# Control_Board.net
KiCad netlist of a schematic drawn in EAGLE
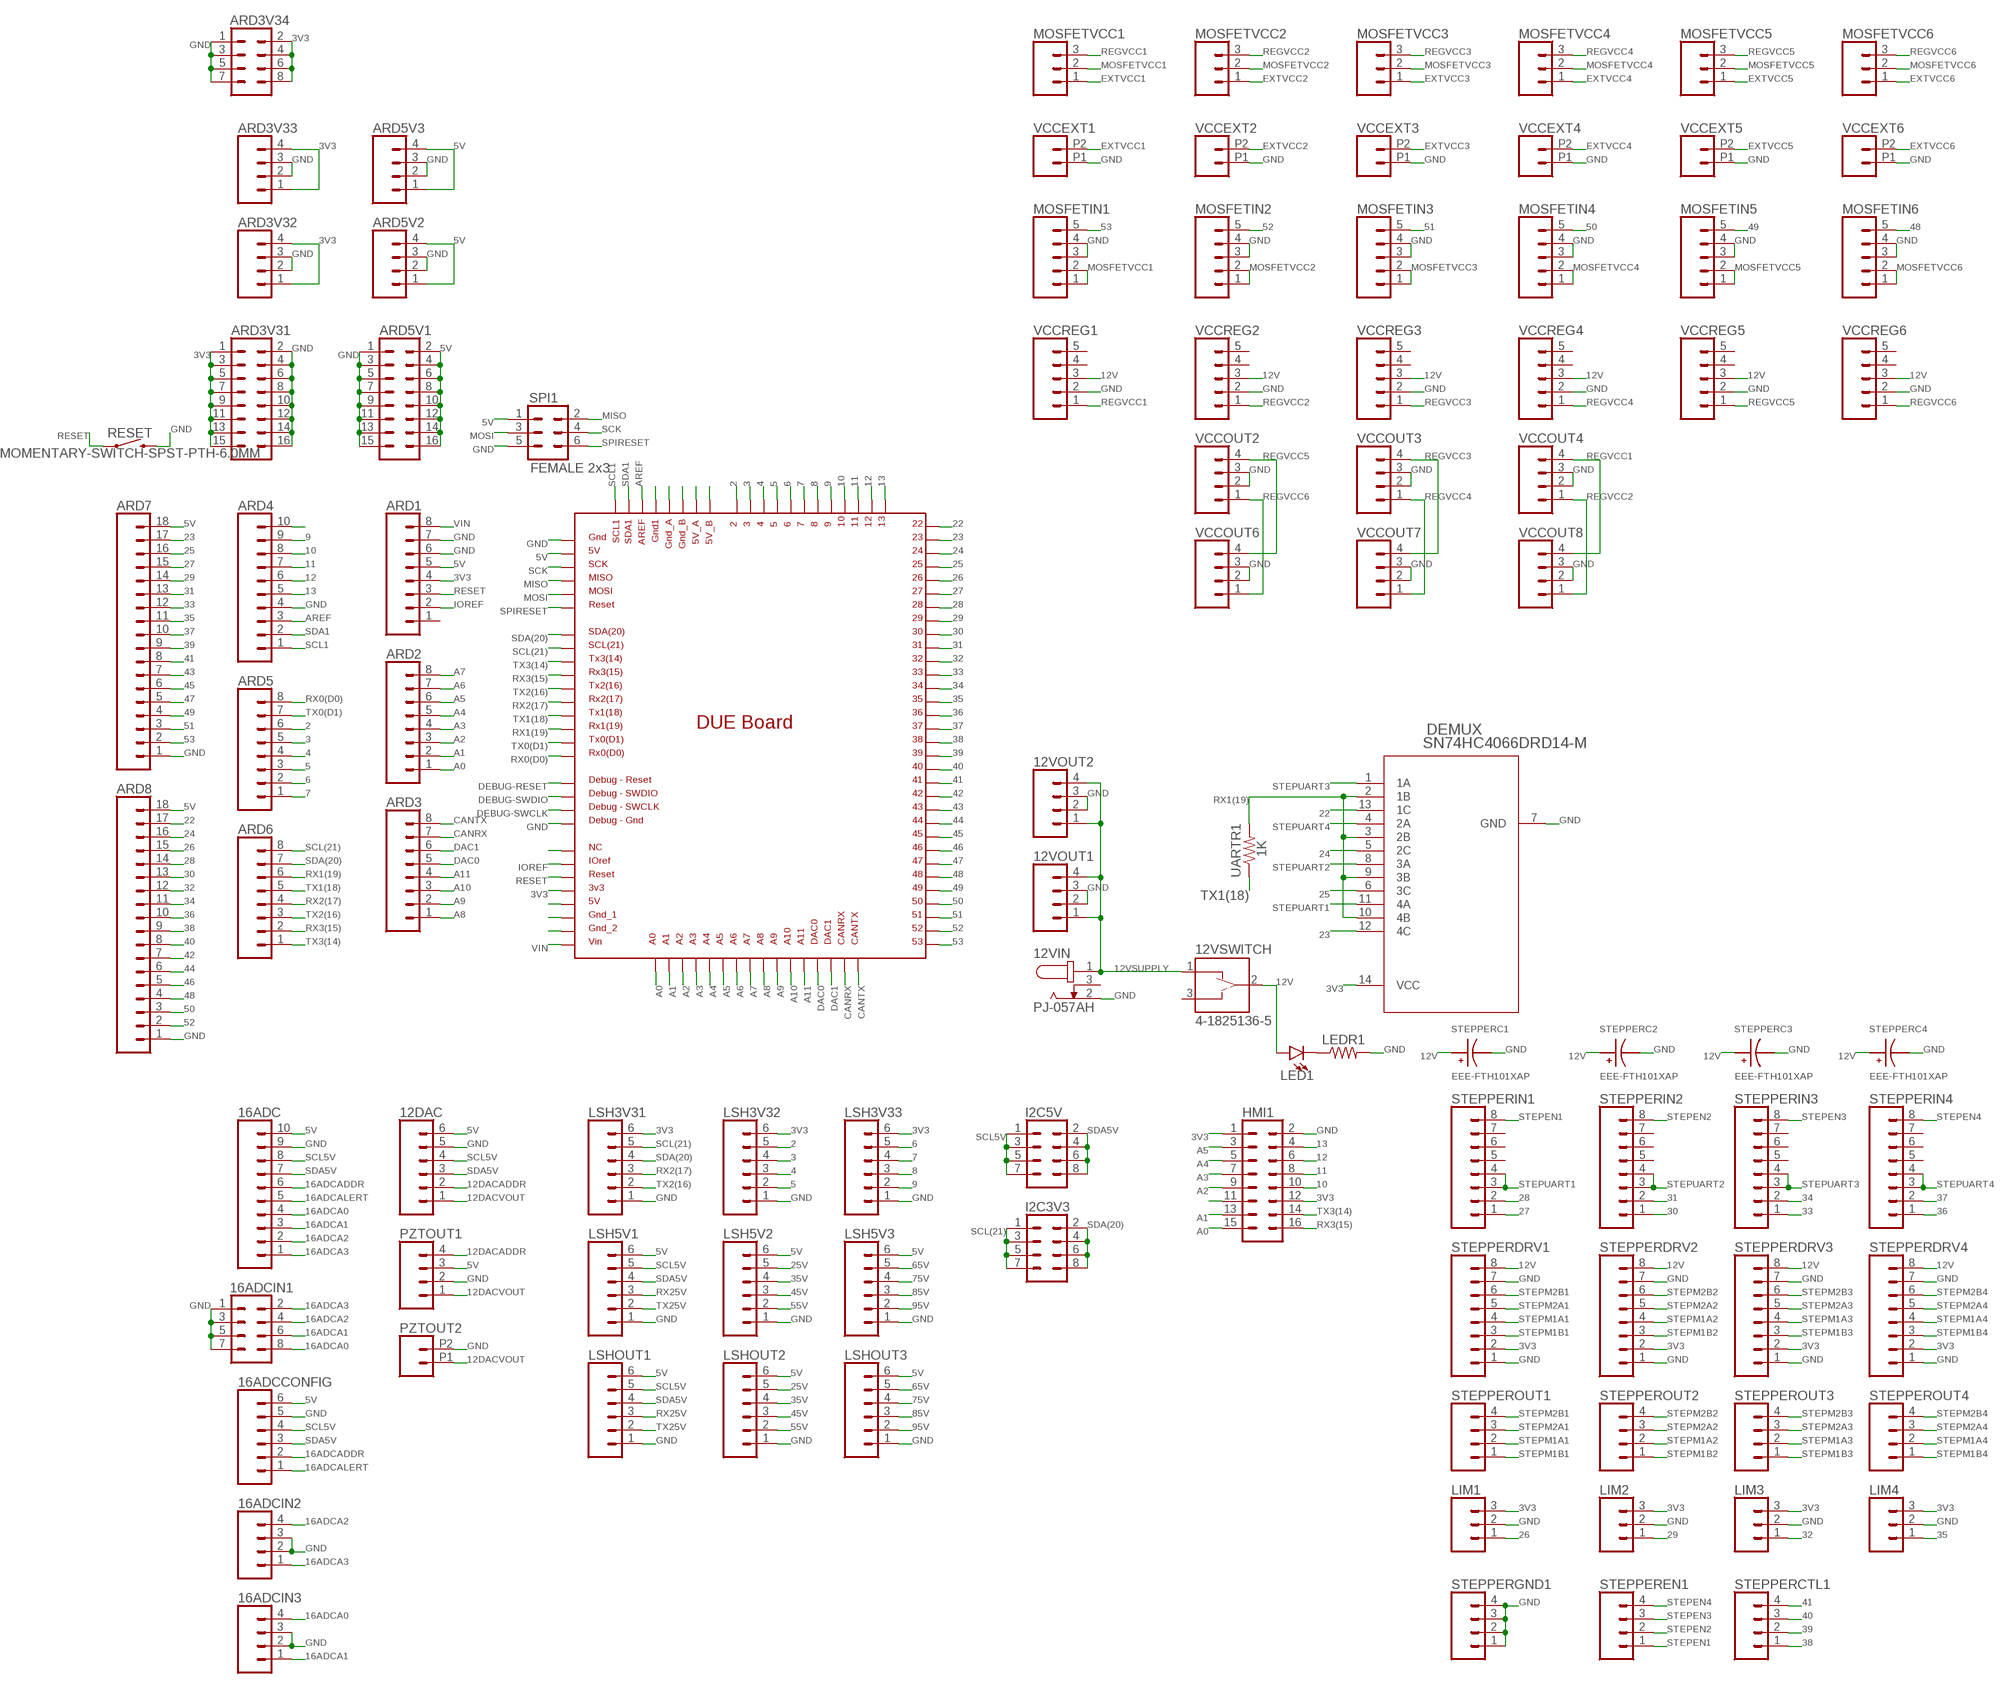
[diagram p0: schematic, sheet 1]

(export (version "E")
  (design (tool "Eeschema 10.0.6"))
  (components
    (comp (ref "12DAC")
      (value "CONN_06LOCK")
      (footprint "eagle-import:1X06_LOCK")
      (libsource (lib "eagle-import") (part "CONN_06LOCK"))
    )
    (comp (ref "12VIN")
      (value "PJ-057AH")
      (footprint "eagle-import:CUI_PJ-057AH")
      (fields (field (name "DIGI-KEY_PART_NUMBER") "CP-057AH-ND") (field (name "MF") "CUI Inc."))
      (libsource (lib "eagle-import") (part "PJ-057AH"))
    )
    (comp (ref "12VOUT1")
      (value "CONN_04POLAR")
      (footprint "eagle-import:MOLEX-1X4")
      (libsource (lib "eagle-import") (part "CONN_04POLAR"))
    )
    (comp (ref "12VOUT2")
      (value "CONN_04POLAR")
      (footprint "eagle-import:MOLEX-1X4")
      (libsource (lib "eagle-import") (part "CONN_04POLAR"))
    )
    (comp (ref "12VSWITCH")
      (value "4-1825136-5")
      (footprint "eagle-import:TE_4-1825136-5")
      (fields (field (name "DIGI-KEY_PART_NUMBER") "450-1784-ND") (field (name "MF") "TE Connectivity"))
      (libsource (lib "eagle-import") (part "4-1825136-5"))
    )
    (comp (ref "16ADC")
      (value "CONN_10LOCK")
      (footprint "eagle-import:1X10_LOCK")
      (libsource (lib "eagle-import") (part "CONN_10LOCK"))
    )
    (comp (ref "16ADCCONFIG")
      (value "CONN_06LOCK")
      (footprint "eagle-import:1X06_LOCK")
      (libsource (lib "eagle-import") (part "CONN_06LOCK"))
    )
    (comp (ref "16ADCIN1")
      (value "CONN_04X2")
      (footprint "eagle-import:2X4")
      (libsource (lib "eagle-import") (part "CONN_04X2"))
    )
    (comp (ref "16ADCIN2")
      (value "CONN_04POLAR")
      (footprint "eagle-import:MOLEX-1X4")
      (libsource (lib "eagle-import") (part "CONN_04POLAR"))
    )
    (comp (ref "16ADCIN3")
      (value "CONN_04POLAR")
      (footprint "eagle-import:MOLEX-1X4")
      (libsource (lib "eagle-import") (part "CONN_04POLAR"))
    )
    (comp (ref "ARD1")
      (value "CONN_08LOCK")
      (footprint "eagle-import:1X08_LOCK")
      (libsource (lib "eagle-import") (part "CONN_08LOCK"))
    )
    (comp (ref "ARD2")
      (value "CONN_08LOCK")
      (footprint "eagle-import:1X08_LOCK")
      (libsource (lib "eagle-import") (part "CONN_08LOCK"))
    )
    (comp (ref "ARD3")
      (value "CONN_08LOCK")
      (footprint "eagle-import:1X08_LOCK")
      (libsource (lib "eagle-import") (part "CONN_08LOCK"))
    )
    (comp (ref "ARD3V31")
      (value "CONN_08X2")
      (footprint "eagle-import:2X8")
      (libsource (lib "eagle-import") (part "CONN_08X2"))
    )
    (comp (ref "ARD3V32")
      (value "CONN_04POLAR")
      (footprint "eagle-import:MOLEX-1X4")
      (libsource (lib "eagle-import") (part "CONN_04POLAR"))
    )
    (comp (ref "ARD3V33")
      (value "CONN_04POLAR")
      (footprint "eagle-import:MOLEX-1X4")
      (libsource (lib "eagle-import") (part "CONN_04POLAR"))
    )
    (comp (ref "ARD3V34")
      (value "CONN_04X2")
      (footprint "eagle-import:2X4")
      (libsource (lib "eagle-import") (part "CONN_04X2"))
    )
    (comp (ref "ARD4")
      (value "CONN_10LOCK")
      (footprint "eagle-import:1X10_LOCK")
      (libsource (lib "eagle-import") (part "CONN_10LOCK"))
    )
    (comp (ref "ARD5")
      (value "CONN_08LOCK")
      (footprint "eagle-import:1X08_LOCK")
      (libsource (lib "eagle-import") (part "CONN_08LOCK"))
    )
    (comp (ref "ARD5V1")
      (value "CONN_08X2")
      (footprint "eagle-import:2X8")
      (libsource (lib "eagle-import") (part "CONN_08X2"))
    )
    (comp (ref "ARD5V2")
      (value "CONN_04POLAR")
      (footprint "eagle-import:MOLEX-1X4")
      (libsource (lib "eagle-import") (part "CONN_04POLAR"))
    )
    (comp (ref "ARD5V3")
      (value "CONN_04POLAR")
      (footprint "eagle-import:MOLEX-1X4")
      (libsource (lib "eagle-import") (part "CONN_04POLAR"))
    )
    (comp (ref "ARD6")
      (value "CONN_08LOCK")
      (footprint "eagle-import:1X08_LOCK")
      (libsource (lib "eagle-import") (part "CONN_08LOCK"))
    )
    (comp (ref "ARD7")
      (value "CONN_18")
      (footprint "eagle-import:1X18")
      (libsource (lib "eagle-import") (part "CONN_18"))
    )
    (comp (ref "ARD8")
      (value "CONN_18")
      (footprint "eagle-import:1X18")
      (libsource (lib "eagle-import") (part "CONN_18"))
    )
    (comp (ref "DEMUX")
      (value "SN74HC4066DRD14-M")
      (footprint "eagle-import:D14-M")
      (fields (field (name "MANUFACTURER_PART_NUMBER") "SN74HC4066DR"))
      (libsource (lib "eagle-import") (part "SN74HC4066DRD14-M"))
    )
    (comp (ref "HMI1")
      (value "CONN_08X2")
      (footprint "eagle-import:2X8")
      (libsource (lib "eagle-import") (part "CONN_08X2"))
    )
    (comp (ref "I2C3V3")
      (value "CONN_04X2")
      (footprint "eagle-import:2X4")
      (libsource (lib "eagle-import") (part "CONN_04X2"))
    )
    (comp (ref "I2C5V")
      (value "CONN_04X2")
      (footprint "eagle-import:2X4")
      (libsource (lib "eagle-import") (part "CONN_04X2"))
    )
    (comp (ref "LED1")
      (value "LED3MM")
      (footprint "eagle-import:LED_3MM")
      (libsource (lib "eagle-import") (part "LED3MM"))
    )
    (comp (ref "LEDR1")
      (value "RESISTORAXIAL-0.3")
      (footprint "eagle-import:AXIAL-0.3")
      (libsource (lib "eagle-import") (part "RESISTORAXIAL-0.3"))
    )
    (comp (ref "LIM1")
      (value "CONN_03LOCK")
      (footprint "eagle-import:1X03_LOCK")
      (libsource (lib "eagle-import") (part "CONN_03LOCK"))
    )
    (comp (ref "LIM2")
      (value "CONN_03LOCK")
      (footprint "eagle-import:1X03_LOCK")
      (libsource (lib "eagle-import") (part "CONN_03LOCK"))
    )
    (comp (ref "LIM3")
      (value "CONN_03LOCK")
      (footprint "eagle-import:1X03_LOCK")
      (libsource (lib "eagle-import") (part "CONN_03LOCK"))
    )
    (comp (ref "LIM4")
      (value "CONN_03LOCK")
      (footprint "eagle-import:1X03_LOCK")
      (libsource (lib "eagle-import") (part "CONN_03LOCK"))
    )
    (comp (ref "LSH3V31")
      (value "CONN_06NO_SILK_FEMALE_PTH")
      (footprint "eagle-import:1X06_NO_SILK")
      (libsource (lib "eagle-import") (part "CONN_06NO_SILK_FEMALE_PTH"))
    )
    (comp (ref "LSH3V32")
      (value "CONN_06NO_SILK_FEMALE_PTH")
      (footprint "eagle-import:1X06_NO_SILK")
      (libsource (lib "eagle-import") (part "CONN_06NO_SILK_FEMALE_PTH"))
    )
    (comp (ref "LSH3V33")
      (value "CONN_06NO_SILK_FEMALE_PTH")
      (footprint "eagle-import:1X06_NO_SILK")
      (libsource (lib "eagle-import") (part "CONN_06NO_SILK_FEMALE_PTH"))
    )
    (comp (ref "LSH5V1")
      (value "CONN_06NO_SILK_FEMALE_PTH")
      (footprint "eagle-import:1X06_NO_SILK")
      (libsource (lib "eagle-import") (part "CONN_06NO_SILK_FEMALE_PTH"))
    )
    (comp (ref "LSH5V2")
      (value "CONN_06NO_SILK_FEMALE_PTH")
      (footprint "eagle-import:1X06_NO_SILK")
      (libsource (lib "eagle-import") (part "CONN_06NO_SILK_FEMALE_PTH"))
    )
    (comp (ref "LSH5V3")
      (value "CONN_06NO_SILK_FEMALE_PTH")
      (footprint "eagle-import:1X06_NO_SILK")
      (libsource (lib "eagle-import") (part "CONN_06NO_SILK_FEMALE_PTH"))
    )
    (comp (ref "LSHOUT1")
      (value "CONN_06LOCK")
      (footprint "eagle-import:1X06_LOCK")
      (libsource (lib "eagle-import") (part "CONN_06LOCK"))
    )
    (comp (ref "LSHOUT2")
      (value "CONN_06LOCK")
      (footprint "eagle-import:1X06_LOCK")
      (libsource (lib "eagle-import") (part "CONN_06LOCK"))
    )
    (comp (ref "LSHOUT3")
      (value "CONN_06LOCK")
      (footprint "eagle-import:1X06_LOCK")
      (libsource (lib "eagle-import") (part "CONN_06LOCK"))
    )
    (comp (ref "MOSFETIN1")
      (value "CONN_05LOCK")
      (footprint "eagle-import:1X05_LOCK")
      (libsource (lib "eagle-import") (part "CONN_05LOCK"))
    )
    (comp (ref "MOSFETIN2")
      (value "CONN_05LOCK")
      (footprint "eagle-import:1X05_LOCK")
      (libsource (lib "eagle-import") (part "CONN_05LOCK"))
    )
    (comp (ref "MOSFETIN3")
      (value "CONN_05LOCK")
      (footprint "eagle-import:1X05_LOCK")
      (libsource (lib "eagle-import") (part "CONN_05LOCK"))
    )
    (comp (ref "MOSFETIN4")
      (value "CONN_05LOCK")
      (footprint "eagle-import:1X05_LOCK")
      (libsource (lib "eagle-import") (part "CONN_05LOCK"))
    )
    (comp (ref "MOSFETIN5")
      (value "CONN_05LOCK")
      (footprint "eagle-import:1X05_LOCK")
      (libsource (lib "eagle-import") (part "CONN_05LOCK"))
    )
    (comp (ref "MOSFETIN6")
      (value "CONN_05LOCK")
      (footprint "eagle-import:1X05_LOCK")
      (libsource (lib "eagle-import") (part "CONN_05LOCK"))
    )
    (comp (ref "MOSFETVCC1")
      (value "CONN_03LOCK")
      (footprint "eagle-import:1X03_LOCK")
      (libsource (lib "eagle-import") (part "CONN_03LOCK"))
    )
    (comp (ref "MOSFETVCC2")
      (value "CONN_03LOCK")
      (footprint "eagle-import:1X03_LOCK")
      (libsource (lib "eagle-import") (part "CONN_03LOCK"))
    )
    (comp (ref "MOSFETVCC3")
      (value "CONN_03LOCK")
      (footprint "eagle-import:1X03_LOCK")
      (libsource (lib "eagle-import") (part "CONN_03LOCK"))
    )
    (comp (ref "MOSFETVCC4")
      (value "CONN_03LOCK")
      (footprint "eagle-import:1X03_LOCK")
      (libsource (lib "eagle-import") (part "CONN_03LOCK"))
    )
    (comp (ref "MOSFETVCC5")
      (value "CONN_03LOCK")
      (footprint "eagle-import:1X03_LOCK")
      (libsource (lib "eagle-import") (part "CONN_03LOCK"))
    )
    (comp (ref "MOSFETVCC6")
      (value "CONN_03LOCK")
      (footprint "eagle-import:1X03_LOCK")
      (libsource (lib "eagle-import") (part "CONN_03LOCK"))
    )
    (comp (ref "PZTOUT1")
      (value "CONN_04LOCK")
      (footprint "eagle-import:1X04_LOCK")
      (libsource (lib "eagle-import") (part "CONN_04LOCK"))
    )
    (comp (ref "PZTOUT2")
      (value "CONN_022.54MM_SCREWTERM")
      (footprint "eagle-import:1X02_2.54_SCREWTERM")
      (libsource (lib "eagle-import") (part "CONN_022.54MM_SCREWTERM"))
    )
    (comp (ref "RESET")
      (value "MOMENTARY-SWITCH-SPST-PTH-6.0MM")
      (footprint "eagle-import:TACTILE_SWITCH_PTH_6.0MM")
      (libsource (lib "eagle-import") (part "MOMENTARY-SWITCH-SPST-PTH-6.0MM"))
    )
    (comp (ref "SPI1")
      (value "FEMALE 2x3")
      (footprint "eagle-import:2X3")
      (libsource (lib "eagle-import") (part "CONN_03X2FEMALE"))
    )
    (comp (ref "STEPPERC1")
      (value "EEE-FTH101XAP")
      (footprint "eagle-import:CAPAE660X800N")
      (fields (field (name "DIGI-KEY_PART_NUMBER") "PCE5024CT-ND") (field (name "MF") "Panasonic Electronic"))
      (libsource (lib "eagle-import") (part "EEE-FTH101XAP"))
    )
    (comp (ref "STEPPERC2")
      (value "EEE-FTH101XAP")
      (footprint "eagle-import:CAPAE660X800N")
      (fields (field (name "DIGI-KEY_PART_NUMBER") "PCE5024CT-ND") (field (name "MF") "Panasonic Electronic"))
      (libsource (lib "eagle-import") (part "EEE-FTH101XAP"))
    )
    (comp (ref "STEPPERC3")
      (value "EEE-FTH101XAP")
      (footprint "eagle-import:CAPAE660X800N")
      (fields (field (name "DIGI-KEY_PART_NUMBER") "PCE5024CT-ND") (field (name "MF") "Panasonic Electronic"))
      (libsource (lib "eagle-import") (part "EEE-FTH101XAP"))
    )
    (comp (ref "STEPPERC4")
      (value "EEE-FTH101XAP")
      (footprint "eagle-import:CAPAE660X800N")
      (fields (field (name "DIGI-KEY_PART_NUMBER") "PCE5024CT-ND") (field (name "MF") "Panasonic Electronic"))
      (libsource (lib "eagle-import") (part "EEE-FTH101XAP"))
    )
    (comp (ref "STEPPERCTL1")
      (value "CONN_04LOCK")
      (footprint "eagle-import:1X04_LOCK")
      (libsource (lib "eagle-import") (part "CONN_04LOCK"))
    )
    (comp (ref "STEPPERDRV1")
      (value "CONN_08NO_SILK_FEMALE_PTH")
      (footprint "eagle-import:1X08_NO_SILK")
      (libsource (lib "eagle-import") (part "CONN_08NO_SILK_FEMALE_PTH"))
    )
    (comp (ref "STEPPERDRV2")
      (value "CONN_08NO_SILK_FEMALE_PTH")
      (footprint "eagle-import:1X08_NO_SILK")
      (libsource (lib "eagle-import") (part "CONN_08NO_SILK_FEMALE_PTH"))
    )
    (comp (ref "STEPPERDRV3")
      (value "CONN_08NO_SILK_FEMALE_PTH")
      (footprint "eagle-import:1X08_NO_SILK")
      (libsource (lib "eagle-import") (part "CONN_08NO_SILK_FEMALE_PTH"))
    )
    (comp (ref "STEPPERDRV4")
      (value "CONN_08NO_SILK_FEMALE_PTH")
      (footprint "eagle-import:1X08_NO_SILK")
      (libsource (lib "eagle-import") (part "CONN_08NO_SILK_FEMALE_PTH"))
    )
    (comp (ref "STEPPEREN1")
      (value "CONN_04LOCK")
      (footprint "eagle-import:1X04_LOCK")
      (libsource (lib "eagle-import") (part "CONN_04LOCK"))
    )
    (comp (ref "STEPPERGND1")
      (value "CONN_04LOCK")
      (footprint "eagle-import:1X04_LOCK")
      (libsource (lib "eagle-import") (part "CONN_04LOCK"))
    )
    (comp (ref "STEPPERIN1")
      (value "CONN_08NO_SILK_FEMALE_PTH")
      (footprint "eagle-import:1X08_NO_SILK")
      (libsource (lib "eagle-import") (part "CONN_08NO_SILK_FEMALE_PTH"))
    )
    (comp (ref "STEPPERIN2")
      (value "CONN_08NO_SILK_FEMALE_PTH")
      (footprint "eagle-import:1X08_NO_SILK")
      (libsource (lib "eagle-import") (part "CONN_08NO_SILK_FEMALE_PTH"))
    )
    (comp (ref "STEPPERIN3")
      (value "CONN_08NO_SILK_FEMALE_PTH")
      (footprint "eagle-import:1X08_NO_SILK")
      (libsource (lib "eagle-import") (part "CONN_08NO_SILK_FEMALE_PTH"))
    )
    (comp (ref "STEPPERIN4")
      (value "CONN_08NO_SILK_FEMALE_PTH")
      (footprint "eagle-import:1X08_NO_SILK")
      (libsource (lib "eagle-import") (part "CONN_08NO_SILK_FEMALE_PTH"))
    )
    (comp (ref "STEPPEROUT1")
      (value "CONN_04POLAR")
      (footprint "eagle-import:MOLEX-1X4")
      (libsource (lib "eagle-import") (part "CONN_04POLAR"))
    )
    (comp (ref "STEPPEROUT2")
      (value "CONN_04POLAR")
      (footprint "eagle-import:MOLEX-1X4")
      (libsource (lib "eagle-import") (part "CONN_04POLAR"))
    )
    (comp (ref "STEPPEROUT3")
      (value "CONN_04POLAR")
      (footprint "eagle-import:MOLEX-1X4")
      (libsource (lib "eagle-import") (part "CONN_04POLAR"))
    )
    (comp (ref "STEPPEROUT4")
      (value "CONN_04POLAR")
      (footprint "eagle-import:MOLEX-1X4")
      (libsource (lib "eagle-import") (part "CONN_04POLAR"))
    )
    (comp (ref "U$1")
      (value "DUE-UPSIDEDOWN")
      (footprint "eagle-import:DUE-UPSIDEDOWN")
      (libsource (lib "eagle-import") (part "DUE-UPSIDEDOWN"))
    )
    (comp (ref "UARTR1")
      (value "1K")
      (footprint "eagle-import:0805")
      (libsource (lib "eagle-import") (part "RESISTOR0805"))
    )
    (comp (ref "VCCEXT1")
      (value "CONN_022.54MM_SCREWTERM")
      (footprint "eagle-import:1X02_2.54_SCREWTERM")
      (libsource (lib "eagle-import") (part "CONN_022.54MM_SCREWTERM"))
    )
    (comp (ref "VCCEXT2")
      (value "CONN_022.54MM_SCREWTERM")
      (footprint "eagle-import:1X02_2.54_SCREWTERM")
      (libsource (lib "eagle-import") (part "CONN_022.54MM_SCREWTERM"))
    )
    (comp (ref "VCCEXT3")
      (value "CONN_022.54MM_SCREWTERM")
      (footprint "eagle-import:1X02_2.54_SCREWTERM")
      (libsource (lib "eagle-import") (part "CONN_022.54MM_SCREWTERM"))
    )
    (comp (ref "VCCEXT4")
      (value "CONN_022.54MM_SCREWTERM")
      (footprint "eagle-import:1X02_2.54_SCREWTERM")
      (libsource (lib "eagle-import") (part "CONN_022.54MM_SCREWTERM"))
    )
    (comp (ref "VCCEXT5")
      (value "CONN_022.54MM_SCREWTERM")
      (footprint "eagle-import:1X02_2.54_SCREWTERM")
      (libsource (lib "eagle-import") (part "CONN_022.54MM_SCREWTERM"))
    )
    (comp (ref "VCCEXT6")
      (value "CONN_022.54MM_SCREWTERM")
      (footprint "eagle-import:1X02_2.54_SCREWTERM")
      (libsource (lib "eagle-import") (part "CONN_022.54MM_SCREWTERM"))
    )
    (comp (ref "VCCOUT2")
      (value "CONN_04LOCK")
      (footprint "eagle-import:1X04_LOCK")
      (libsource (lib "eagle-import") (part "CONN_04LOCK"))
    )
    (comp (ref "VCCOUT3")
      (value "CONN_04LOCK")
      (footprint "eagle-import:1X04_LOCK")
      (libsource (lib "eagle-import") (part "CONN_04LOCK"))
    )
    (comp (ref "VCCOUT4")
      (value "CONN_04LOCK")
      (footprint "eagle-import:1X04_LOCK")
      (libsource (lib "eagle-import") (part "CONN_04LOCK"))
    )
    (comp (ref "VCCOUT6")
      (value "CONN_04POLAR")
      (footprint "eagle-import:MOLEX-1X4")
      (libsource (lib "eagle-import") (part "CONN_04POLAR"))
    )
    (comp (ref "VCCOUT7")
      (value "CONN_04POLAR")
      (footprint "eagle-import:MOLEX-1X4")
      (libsource (lib "eagle-import") (part "CONN_04POLAR"))
    )
    (comp (ref "VCCOUT8")
      (value "CONN_04POLAR")
      (footprint "eagle-import:MOLEX-1X4")
      (libsource (lib "eagle-import") (part "CONN_04POLAR"))
    )
    (comp (ref "VCCREG1")
      (value "CONN_05LOCK")
      (footprint "eagle-import:1X05_LOCK")
      (libsource (lib "eagle-import") (part "CONN_05LOCK"))
    )
    (comp (ref "VCCREG2")
      (value "CONN_05LOCK")
      (footprint "eagle-import:1X05_LOCK")
      (libsource (lib "eagle-import") (part "CONN_05LOCK"))
    )
    (comp (ref "VCCREG3")
      (value "CONN_05LOCK")
      (footprint "eagle-import:1X05_LOCK")
      (libsource (lib "eagle-import") (part "CONN_05LOCK"))
    )
    (comp (ref "VCCREG4")
      (value "CONN_05LOCK")
      (footprint "eagle-import:1X05_LOCK")
      (libsource (lib "eagle-import") (part "CONN_05LOCK"))
    )
    (comp (ref "VCCREG5")
      (value "CONN_05LOCK")
      (footprint "eagle-import:1X05_LOCK")
      (libsource (lib "eagle-import") (part "CONN_05LOCK"))
    )
    (comp (ref "VCCREG6")
      (value "CONN_05LOCK")
      (footprint "eagle-import:1X05_LOCK")
      (libsource (lib "eagle-import") (part "CONN_05LOCK"))
    )
  )
  (nets
    (net (code "1") (name "/2") (class "Default")
      (node (ref "ARD5") (pin "6") (pinfunction "6_6") (pintype "passive"))
      (node (ref "LSH3V32") (pin "5") (pinfunction "5_5") (pintype "passive"))
      (node (ref "U$1") (pin "2") (pinfunction "2_2") (pintype "bidirectional"))
    )
    (net (code "2") (name "/3") (class "Default")
      (node (ref "ARD5") (pin "5") (pinfunction "5_5") (pintype "passive"))
      (node (ref "LSH3V32") (pin "4") (pinfunction "4_4") (pintype "passive"))
      (node (ref "U$1") (pin "3") (pinfunction "3_3") (pintype "bidirectional"))
    )
    (net (code "3") (name "/3V3") (class "Default")
      (node (ref "ARD1") (pin "4") (pinfunction "4_4") (pintype "passive"))
      (node (ref "ARD3V31") (pin "1") (pinfunction "1_1") (pintype "passive"))
      (node (ref "ARD3V31") (pin "11") (pinfunction "11_11") (pintype "passive"))
      (node (ref "ARD3V31") (pin "13") (pinfunction "13_13") (pintype "passive"))
      (node (ref "ARD3V31") (pin "15") (pinfunction "15_15") (pintype "passive"))
      (node (ref "ARD3V31") (pin "3") (pinfunction "3_3") (pintype "passive"))
      (node (ref "ARD3V31") (pin "5") (pinfunction "5_5") (pintype "passive"))
      (node (ref "ARD3V31") (pin "7") (pinfunction "7_7") (pintype "passive"))
      (node (ref "ARD3V31") (pin "9") (pinfunction "9_9") (pintype "passive"))
      (node (ref "ARD3V32") (pin "1") (pinfunction "1_1") (pintype "passive"))
      (node (ref "ARD3V32") (pin "4") (pinfunction "4_4") (pintype "passive"))
      (node (ref "ARD3V33") (pin "1") (pinfunction "1_1") (pintype "passive"))
      (node (ref "ARD3V33") (pin "4") (pinfunction "4_4") (pintype "passive"))
      (node (ref "ARD3V34") (pin "2") (pinfunction "2_2") (pintype "passive"))
      (node (ref "ARD3V34") (pin "4") (pinfunction "4_4") (pintype "passive"))
      (node (ref "ARD3V34") (pin "6") (pinfunction "6_6") (pintype "passive"))
      (node (ref "ARD3V34") (pin "8") (pinfunction "8_8") (pintype "passive"))
      (node (ref "DEMUX") (pin "14") (pinfunction "VCC_14") (pintype "power_in"))
      (node (ref "HMI1") (pin "1") (pinfunction "1_1") (pintype "passive"))
      (node (ref "HMI1") (pin "12") (pinfunction "12_12") (pintype "passive"))
      (node (ref "LIM1") (pin "3") (pinfunction "3_3") (pintype "passive"))
      (node (ref "LIM2") (pin "3") (pinfunction "3_3") (pintype "passive"))
      (node (ref "LIM3") (pin "3") (pinfunction "3_3") (pintype "passive"))
      (node (ref "LIM4") (pin "3") (pinfunction "3_3") (pintype "passive"))
      (node (ref "LSH3V31") (pin "6") (pinfunction "6_6") (pintype "passive"))
      (node (ref "LSH3V32") (pin "6") (pinfunction "6_6") (pintype "passive"))
      (node (ref "LSH3V33") (pin "6") (pinfunction "6_6") (pintype "passive"))
      (node (ref "STEPPERDRV1") (pin "2") (pinfunction "2_2") (pintype "passive"))
      (node (ref "STEPPERDRV2") (pin "2") (pinfunction "2_2") (pintype "passive"))
      (node (ref "STEPPERDRV3") (pin "2") (pinfunction "2_2") (pintype "passive"))
      (node (ref "STEPPERDRV4") (pin "2") (pinfunction "2_2") (pintype "passive"))
      (node (ref "U$1") (pin "3V3") (pinfunction "3V3_3V3") (pintype "bidirectional"))
    )
    (net (code "4") (name "/4") (class "Default")
      (node (ref "ARD5") (pin "4") (pinfunction "4_4") (pintype "passive"))
      (node (ref "LSH3V32") (pin "3") (pinfunction "3_3") (pintype "passive"))
      (node (ref "U$1") (pin "4") (pinfunction "4_4") (pintype "bidirectional"))
    )
    (net (code "5") (name "/5") (class "Default")
      (node (ref "ARD5") (pin "3") (pinfunction "3_3") (pintype "passive"))
      (node (ref "LSH3V32") (pin "2") (pinfunction "2_2") (pintype "passive"))
      (node (ref "U$1") (pin "5") (pinfunction "5_5") (pintype "bidirectional"))
    )
    (net (code "6") (name "/5V") (class "Default")
      (node (ref "12DAC") (pin "6") (pinfunction "6_6") (pintype "passive"))
      (node (ref "16ADC") (pin "10") (pinfunction "10_10") (pintype "passive"))
      (node (ref "16ADCCONFIG") (pin "6") (pinfunction "6_6") (pintype "passive"))
      (node (ref "ARD1") (pin "5") (pinfunction "5_5") (pintype "passive"))
      (node (ref "ARD5V1") (pin "10") (pinfunction "10_10") (pintype "passive"))
      (node (ref "ARD5V1") (pin "12") (pinfunction "12_12") (pintype "passive"))
      (node (ref "ARD5V1") (pin "14") (pinfunction "14_14") (pintype "passive"))
      (node (ref "ARD5V1") (pin "16") (pinfunction "16_16") (pintype "passive"))
      (node (ref "ARD5V1") (pin "2") (pinfunction "2_2") (pintype "passive"))
      (node (ref "ARD5V1") (pin "4") (pinfunction "4_4") (pintype "passive"))
      (node (ref "ARD5V1") (pin "6") (pinfunction "6_6") (pintype "passive"))
      (node (ref "ARD5V1") (pin "8") (pinfunction "8_8") (pintype "passive"))
      (node (ref "ARD5V2") (pin "1") (pinfunction "1_1") (pintype "passive"))
      (node (ref "ARD5V2") (pin "4") (pinfunction "4_4") (pintype "passive"))
      (node (ref "ARD5V3") (pin "1") (pinfunction "1_1") (pintype "passive"))
      (node (ref "ARD5V3") (pin "4") (pinfunction "4_4") (pintype "passive"))
      (node (ref "ARD7") (pin "18") (pinfunction "18_18") (pintype "passive"))
      (node (ref "ARD8") (pin "18") (pinfunction "18_18") (pintype "passive"))
      (node (ref "LSH5V1") (pin "6") (pinfunction "6_6") (pintype "passive"))
      (node (ref "LSH5V2") (pin "6") (pinfunction "6_6") (pintype "passive"))
      (node (ref "LSH5V3") (pin "6") (pinfunction "6_6") (pintype "passive"))
      (node (ref "LSHOUT1") (pin "6") (pinfunction "6_6") (pintype "passive"))
      (node (ref "LSHOUT2") (pin "6") (pinfunction "6_6") (pintype "passive"))
      (node (ref "LSHOUT3") (pin "6") (pinfunction "6_6") (pintype "passive"))
      (node (ref "PZTOUT1") (pin "3") (pinfunction "3_3") (pintype "passive"))
      (node (ref "SPI1") (pin "1") (pinfunction "1_1") (pintype "bidirectional"))
      (node (ref "U$1") (pin "5V") (pinfunction "5V_5V") (pintype "bidirectional"))
      (node (ref "U$1") (pin "5V_A") (pinfunction "5V_A_5V_A") (pintype "bidirectional"))
      (node (ref "U$1") (pin "5V_B") (pinfunction "5V_B_5V_B") (pintype "bidirectional"))
      (node (ref "U$1") (pin "GND_ICSP") (pinfunction "GND_ICSP_GND_ICSP") (pintype "bidirectional"))
    )
    (net (code "7") (name "/6") (class "Default")
      (node (ref "ARD5") (pin "2") (pinfunction "2_2") (pintype "passive"))
      (node (ref "LSH3V33") (pin "5") (pinfunction "5_5") (pintype "passive"))
      (node (ref "U$1") (pin "6") (pinfunction "6_6") (pintype "bidirectional"))
    )
    (net (code "8") (name "/7") (class "Default")
      (node (ref "ARD5") (pin "1") (pinfunction "1_1") (pintype "passive"))
      (node (ref "LSH3V33") (pin "4") (pinfunction "4_4") (pintype "passive"))
      (node (ref "U$1") (pin "7") (pinfunction "7_7") (pintype "bidirectional"))
    )
    (net (code "9") (name "/8") (class "Default")
      (node (ref "ARD4") (pin "10") (pinfunction "10_10") (pintype "passive"))
      (node (ref "LSH3V33") (pin "3") (pinfunction "3_3") (pintype "passive"))
      (node (ref "U$1") (pin "8") (pinfunction "8_8") (pintype "bidirectional"))
    )
    (net (code "10") (name "/9") (class "Default")
      (node (ref "ARD4") (pin "9") (pinfunction "9_9") (pintype "passive"))
      (node (ref "LSH3V33") (pin "2") (pinfunction "2_2") (pintype "passive"))
      (node (ref "U$1") (pin "9") (pinfunction "9_9") (pintype "bidirectional"))
    )
    (net (code "11") (name "/10") (class "Default")
      (node (ref "ARD4") (pin "8") (pinfunction "8_8") (pintype "passive"))
      (node (ref "HMI1") (pin "10") (pinfunction "10_10") (pintype "passive"))
      (node (ref "U$1") (pin "10") (pinfunction "10_10") (pintype "bidirectional"))
    )
    (net (code "12") (name "/11") (class "Default")
      (node (ref "ARD4") (pin "7") (pinfunction "7_7") (pintype "passive"))
      (node (ref "HMI1") (pin "8") (pinfunction "8_8") (pintype "passive"))
      (node (ref "U$1") (pin "11") (pinfunction "11_11") (pintype "bidirectional"))
    )
    (net (code "13") (name "/12") (class "Default")
      (node (ref "ARD4") (pin "6") (pinfunction "6_6") (pintype "passive"))
      (node (ref "HMI1") (pin "6") (pinfunction "6_6") (pintype "passive"))
      (node (ref "U$1") (pin "12") (pinfunction "12_12") (pintype "bidirectional"))
    )
    (net (code "14") (name "/12DACADDR") (class "Default")
      (node (ref "12DAC") (pin "2") (pinfunction "2_2") (pintype "passive"))
      (node (ref "PZTOUT1") (pin "4") (pinfunction "4_4") (pintype "passive"))
    )
    (net (code "15") (name "/12DACVOUT") (class "Default")
      (node (ref "12DAC") (pin "1") (pinfunction "1_1") (pintype "passive"))
      (node (ref "PZTOUT1") (pin "1") (pinfunction "1_1") (pintype "passive"))
      (node (ref "PZTOUT2") (pin "P1") (pinfunction "1_P1") (pintype "passive"))
    )
    (net (code "16") (name "/12V") (class "Default")
      (node (ref "12VSWITCH") (pin "2") (pinfunction "2_2") (pintype "passive"))
      (node (ref "LED1") (pin "A") (pinfunction "A_A") (pintype "passive"))
      (node (ref "STEPPERC1") (pin "1") (pinfunction "1_1") (pintype "passive"))
      (node (ref "STEPPERC2") (pin "1") (pinfunction "1_1") (pintype "passive"))
      (node (ref "STEPPERC3") (pin "1") (pinfunction "1_1") (pintype "passive"))
      (node (ref "STEPPERC4") (pin "1") (pinfunction "1_1") (pintype "passive"))
      (node (ref "STEPPERDRV1") (pin "8") (pinfunction "8_8") (pintype "passive"))
      (node (ref "STEPPERDRV2") (pin "8") (pinfunction "8_8") (pintype "passive"))
      (node (ref "STEPPERDRV3") (pin "8") (pinfunction "8_8") (pintype "passive"))
      (node (ref "STEPPERDRV4") (pin "8") (pinfunction "8_8") (pintype "passive"))
      (node (ref "VCCREG1") (pin "3") (pinfunction "3_3") (pintype "passive"))
      (node (ref "VCCREG2") (pin "3") (pinfunction "3_3") (pintype "passive"))
      (node (ref "VCCREG3") (pin "3") (pinfunction "3_3") (pintype "passive"))
      (node (ref "VCCREG4") (pin "3") (pinfunction "3_3") (pintype "passive"))
      (node (ref "VCCREG5") (pin "3") (pinfunction "3_3") (pintype "passive"))
      (node (ref "VCCREG6") (pin "3") (pinfunction "3_3") (pintype "passive"))
    )
    (net (code "17") (name "/12VSUPPLY") (class "Default")
      (node (ref "12VIN") (pin "1") (pinfunction "1_1") (pintype "passive"))
      (node (ref "12VOUT1") (pin "1") (pinfunction "1_1") (pintype "passive"))
      (node (ref "12VOUT1") (pin "4") (pinfunction "4_4") (pintype "passive"))
      (node (ref "12VOUT2") (pin "1") (pinfunction "1_1") (pintype "passive"))
      (node (ref "12VOUT2") (pin "4") (pinfunction "4_4") (pintype "passive"))
      (node (ref "12VSWITCH") (pin "1") (pinfunction "1_1") (pintype "passive"))
    )
    (net (code "18") (name "/13") (class "Default")
      (node (ref "ARD4") (pin "5") (pinfunction "5_5") (pintype "passive"))
      (node (ref "HMI1") (pin "4") (pinfunction "4_4") (pintype "passive"))
      (node (ref "U$1") (pin "13") (pinfunction "13_13") (pintype "bidirectional"))
    )
    (net (code "19") (name "/16ADCA0") (class "Default")
      (node (ref "16ADC") (pin "4") (pinfunction "4_4") (pintype "passive"))
      (node (ref "16ADCIN1") (pin "8") (pinfunction "8_8") (pintype "passive"))
      (node (ref "16ADCIN3") (pin "4") (pinfunction "4_4") (pintype "passive"))
    )
    (net (code "20") (name "/16ADCA1") (class "Default")
      (node (ref "16ADC") (pin "3") (pinfunction "3_3") (pintype "passive"))
      (node (ref "16ADCIN1") (pin "6") (pinfunction "6_6") (pintype "passive"))
      (node (ref "16ADCIN3") (pin "1") (pinfunction "1_1") (pintype "passive"))
    )
    (net (code "21") (name "/16ADCA2") (class "Default")
      (node (ref "16ADC") (pin "2") (pinfunction "2_2") (pintype "passive"))
      (node (ref "16ADCIN1") (pin "4") (pinfunction "4_4") (pintype "passive"))
      (node (ref "16ADCIN2") (pin "4") (pinfunction "4_4") (pintype "passive"))
    )
    (net (code "22") (name "/16ADCA3") (class "Default")
      (node (ref "16ADC") (pin "1") (pinfunction "1_1") (pintype "passive"))
      (node (ref "16ADCIN1") (pin "2") (pinfunction "2_2") (pintype "passive"))
      (node (ref "16ADCIN2") (pin "1") (pinfunction "1_1") (pintype "passive"))
    )
    (net (code "23") (name "/16ADCADDR") (class "Default")
      (node (ref "16ADC") (pin "6") (pinfunction "6_6") (pintype "passive"))
      (node (ref "16ADCCONFIG") (pin "2") (pinfunction "2_2") (pintype "passive"))
    )
    (net (code "24") (name "/16ADCALERT") (class "Default")
      (node (ref "16ADC") (pin "5") (pinfunction "5_5") (pintype "passive"))
      (node (ref "16ADCCONFIG") (pin "1") (pinfunction "1_1") (pintype "passive"))
    )
    (net (code "25") (name "/22") (class "Default")
      (node (ref "ARD8") (pin "17") (pinfunction "17_17") (pintype "passive"))
      (node (ref "DEMUX") (pin "13") (pinfunction "1C_13") (pintype "input"))
      (node (ref "U$1") (pin "22") (pinfunction "22_22") (pintype "bidirectional"))
    )
    (net (code "26") (name "/23") (class "Default")
      (node (ref "ARD7") (pin "17") (pinfunction "17_17") (pintype "passive"))
      (node (ref "DEMUX") (pin "12") (pinfunction "4C_12") (pintype "input"))
      (node (ref "U$1") (pin "23") (pinfunction "23_23") (pintype "bidirectional"))
    )
    (net (code "27") (name "/24") (class "Default")
      (node (ref "ARD8") (pin "16") (pinfunction "16_16") (pintype "passive"))
      (node (ref "DEMUX") (pin "5") (pinfunction "2C_5") (pintype "input"))
      (node (ref "U$1") (pin "24") (pinfunction "24_24") (pintype "bidirectional"))
    )
    (net (code "28") (name "/25") (class "Default")
      (node (ref "ARD7") (pin "16") (pinfunction "16_16") (pintype "passive"))
      (node (ref "DEMUX") (pin "6") (pinfunction "3C_6") (pintype "input"))
      (node (ref "U$1") (pin "25") (pinfunction "25_25") (pintype "bidirectional"))
    )
    (net (code "29") (name "/25V") (class "Default")
      (node (ref "LSH5V2") (pin "5") (pinfunction "5_5") (pintype "passive"))
      (node (ref "LSHOUT2") (pin "5") (pinfunction "5_5") (pintype "passive"))
    )
    (net (code "30") (name "/26") (class "Default")
      (node (ref "ARD8") (pin "15") (pinfunction "15_15") (pintype "passive"))
      (node (ref "LIM1") (pin "1") (pinfunction "1_1") (pintype "passive"))
      (node (ref "U$1") (pin "26") (pinfunction "26_26") (pintype "bidirectional"))
    )
    (net (code "31") (name "/27") (class "Default")
      (node (ref "ARD7") (pin "15") (pinfunction "15_15") (pintype "passive"))
      (node (ref "STEPPERIN1") (pin "1") (pinfunction "1_1") (pintype "passive"))
      (node (ref "U$1") (pin "27") (pinfunction "27_27") (pintype "bidirectional"))
    )
    (net (code "32") (name "/28") (class "Default")
      (node (ref "ARD8") (pin "14") (pinfunction "14_14") (pintype "passive"))
      (node (ref "STEPPERIN1") (pin "2") (pinfunction "2_2") (pintype "passive"))
      (node (ref "U$1") (pin "28") (pinfunction "28_28") (pintype "bidirectional"))
    )
    (net (code "33") (name "/29") (class "Default")
      (node (ref "ARD7") (pin "14") (pinfunction "14_14") (pintype "passive"))
      (node (ref "LIM2") (pin "1") (pinfunction "1_1") (pintype "passive"))
      (node (ref "U$1") (pin "29") (pinfunction "29_29") (pintype "bidirectional"))
    )
    (net (code "34") (name "/30") (class "Default")
      (node (ref "ARD8") (pin "13") (pinfunction "13_13") (pintype "passive"))
      (node (ref "STEPPERIN2") (pin "1") (pinfunction "1_1") (pintype "passive"))
      (node (ref "U$1") (pin "30") (pinfunction "30_30") (pintype "bidirectional"))
    )
    (net (code "35") (name "/31") (class "Default")
      (node (ref "ARD7") (pin "13") (pinfunction "13_13") (pintype "passive"))
      (node (ref "STEPPERIN2") (pin "2") (pinfunction "2_2") (pintype "passive"))
      (node (ref "U$1") (pin "31") (pinfunction "31_31") (pintype "bidirectional"))
    )
    (net (code "36") (name "/32") (class "Default")
      (node (ref "ARD8") (pin "12") (pinfunction "12_12") (pintype "passive"))
      (node (ref "LIM3") (pin "1") (pinfunction "1_1") (pintype "passive"))
      (node (ref "U$1") (pin "32") (pinfunction "32_32") (pintype "bidirectional"))
    )
    (net (code "37") (name "/33") (class "Default")
      (node (ref "ARD7") (pin "12") (pinfunction "12_12") (pintype "passive"))
      (node (ref "STEPPERIN3") (pin "1") (pinfunction "1_1") (pintype "passive"))
      (node (ref "U$1") (pin "33") (pinfunction "33_33") (pintype "bidirectional"))
    )
    (net (code "38") (name "/34") (class "Default")
      (node (ref "ARD8") (pin "11") (pinfunction "11_11") (pintype "passive"))
      (node (ref "STEPPERIN3") (pin "2") (pinfunction "2_2") (pintype "passive"))
      (node (ref "U$1") (pin "34") (pinfunction "34_34") (pintype "bidirectional"))
    )
    (net (code "39") (name "/35") (class "Default")
      (node (ref "ARD7") (pin "11") (pinfunction "11_11") (pintype "passive"))
      (node (ref "LIM4") (pin "1") (pinfunction "1_1") (pintype "passive"))
      (node (ref "U$1") (pin "35") (pinfunction "35_35") (pintype "bidirectional"))
    )
    (net (code "40") (name "/35V") (class "Default")
      (node (ref "LSH5V2") (pin "4") (pinfunction "4_4") (pintype "passive"))
      (node (ref "LSHOUT2") (pin "4") (pinfunction "4_4") (pintype "passive"))
    )
    (net (code "41") (name "/36") (class "Default")
      (node (ref "ARD8") (pin "10") (pinfunction "10_10") (pintype "passive"))
      (node (ref "STEPPERIN4") (pin "1") (pinfunction "1_1") (pintype "passive"))
      (node (ref "U$1") (pin "36") (pinfunction "36_36") (pintype "bidirectional"))
    )
    (net (code "42") (name "/37") (class "Default")
      (node (ref "ARD7") (pin "10") (pinfunction "10_10") (pintype "passive"))
      (node (ref "STEPPERIN4") (pin "2") (pinfunction "2_2") (pintype "passive"))
      (node (ref "U$1") (pin "37") (pinfunction "37_37") (pintype "bidirectional"))
    )
    (net (code "43") (name "/38") (class "Default")
      (node (ref "ARD8") (pin "9") (pinfunction "9_9") (pintype "passive"))
      (node (ref "STEPPERCTL1") (pin "1") (pinfunction "1_1") (pintype "passive"))
      (node (ref "U$1") (pin "38") (pinfunction "38_38") (pintype "bidirectional"))
    )
    (net (code "44") (name "/39") (class "Default")
      (node (ref "ARD7") (pin "9") (pinfunction "9_9") (pintype "passive"))
      (node (ref "STEPPERCTL1") (pin "2") (pinfunction "2_2") (pintype "passive"))
      (node (ref "U$1") (pin "39") (pinfunction "39_39") (pintype "bidirectional"))
    )
    (net (code "45") (name "/40") (class "Default")
      (node (ref "ARD8") (pin "8") (pinfunction "8_8") (pintype "passive"))
      (node (ref "STEPPERCTL1") (pin "3") (pinfunction "3_3") (pintype "passive"))
      (node (ref "U$1") (pin "40") (pinfunction "40_40") (pintype "bidirectional"))
    )
    (net (code "46") (name "/41") (class "Default")
      (node (ref "ARD7") (pin "8") (pinfunction "8_8") (pintype "passive"))
      (node (ref "STEPPERCTL1") (pin "4") (pinfunction "4_4") (pintype "passive"))
      (node (ref "U$1") (pin "41") (pinfunction "41_41") (pintype "bidirectional"))
    )
    (net (code "47") (name "/42") (class "Default")
      (node (ref "ARD8") (pin "7") (pinfunction "7_7") (pintype "passive"))
      (node (ref "U$1") (pin "42") (pinfunction "42_42") (pintype "bidirectional"))
    )
    (net (code "48") (name "/43") (class "Default")
      (node (ref "ARD7") (pin "7") (pinfunction "7_7") (pintype "passive"))
      (node (ref "U$1") (pin "43") (pinfunction "43_43") (pintype "bidirectional"))
    )
    (net (code "49") (name "/44") (class "Default")
      (node (ref "ARD8") (pin "6") (pinfunction "6_6") (pintype "passive"))
      (node (ref "U$1") (pin "44") (pinfunction "44_44") (pintype "bidirectional"))
    )
    (net (code "50") (name "/45") (class "Default")
      (node (ref "ARD7") (pin "6") (pinfunction "6_6") (pintype "passive"))
      (node (ref "U$1") (pin "45") (pinfunction "45_45") (pintype "bidirectional"))
    )
    (net (code "51") (name "/45V") (class "Default")
      (node (ref "LSH5V2") (pin "3") (pinfunction "3_3") (pintype "passive"))
      (node (ref "LSHOUT2") (pin "3") (pinfunction "3_3") (pintype "passive"))
    )
    (net (code "52") (name "/46") (class "Default")
      (node (ref "ARD8") (pin "5") (pinfunction "5_5") (pintype "passive"))
      (node (ref "U$1") (pin "46") (pinfunction "46_46") (pintype "bidirectional"))
    )
    (net (code "53") (name "/47") (class "Default")
      (node (ref "ARD7") (pin "5") (pinfunction "5_5") (pintype "passive"))
      (node (ref "U$1") (pin "47") (pinfunction "47_47") (pintype "bidirectional"))
    )
    (net (code "54") (name "/48") (class "Default")
      (node (ref "ARD8") (pin "4") (pinfunction "4_4") (pintype "passive"))
      (node (ref "MOSFETIN6") (pin "5") (pinfunction "5_5") (pintype "passive"))
      (node (ref "U$1") (pin "48") (pinfunction "48_48") (pintype "bidirectional"))
    )
    (net (code "55") (name "/49") (class "Default")
      (node (ref "ARD7") (pin "4") (pinfunction "4_4") (pintype "passive"))
      (node (ref "MOSFETIN5") (pin "5") (pinfunction "5_5") (pintype "passive"))
      (node (ref "U$1") (pin "49") (pinfunction "49_49") (pintype "bidirectional"))
    )
    (net (code "56") (name "/50") (class "Default")
      (node (ref "ARD8") (pin "3") (pinfunction "3_3") (pintype "passive"))
      (node (ref "MOSFETIN4") (pin "5") (pinfunction "5_5") (pintype "passive"))
      (node (ref "U$1") (pin "50") (pinfunction "50_50") (pintype "bidirectional"))
    )
    (net (code "57") (name "/51") (class "Default")
      (node (ref "ARD7") (pin "3") (pinfunction "3_3") (pintype "passive"))
      (node (ref "MOSFETIN3") (pin "5") (pinfunction "5_5") (pintype "passive"))
      (node (ref "U$1") (pin "51") (pinfunction "51_51") (pintype "bidirectional"))
    )
    (net (code "58") (name "/52") (class "Default")
      (node (ref "ARD8") (pin "2") (pinfunction "2_2") (pintype "passive"))
      (node (ref "MOSFETIN2") (pin "5") (pinfunction "5_5") (pintype "passive"))
      (node (ref "U$1") (pin "52") (pinfunction "52_52") (pintype "bidirectional"))
    )
    (net (code "59") (name "/53") (class "Default")
      (node (ref "ARD7") (pin "2") (pinfunction "2_2") (pintype "passive"))
      (node (ref "MOSFETIN1") (pin "5") (pinfunction "5_5") (pintype "passive"))
      (node (ref "U$1") (pin "53") (pinfunction "53_53") (pintype "bidirectional"))
    )
    (net (code "60") (name "/55V") (class "Default")
      (node (ref "LSH5V2") (pin "2") (pinfunction "2_2") (pintype "passive"))
      (node (ref "LSHOUT2") (pin "2") (pinfunction "2_2") (pintype "passive"))
    )
    (net (code "61") (name "/65V") (class "Default")
      (node (ref "LSH5V3") (pin "5") (pinfunction "5_5") (pintype "passive"))
      (node (ref "LSHOUT3") (pin "5") (pinfunction "5_5") (pintype "passive"))
    )
    (net (code "62") (name "/75V") (class "Default")
      (node (ref "LSH5V3") (pin "4") (pinfunction "4_4") (pintype "passive"))
      (node (ref "LSHOUT3") (pin "4") (pinfunction "4_4") (pintype "passive"))
    )
    (net (code "63") (name "/85V") (class "Default")
      (node (ref "LSH5V3") (pin "3") (pinfunction "3_3") (pintype "passive"))
      (node (ref "LSHOUT3") (pin "3") (pinfunction "3_3") (pintype "passive"))
    )
    (net (code "64") (name "/95V") (class "Default")
      (node (ref "LSH5V3") (pin "2") (pinfunction "2_2") (pintype "passive"))
      (node (ref "LSHOUT3") (pin "2") (pinfunction "2_2") (pintype "passive"))
    )
    (net (code "65") (name "/A0") (class "Default")
      (node (ref "ARD2") (pin "1") (pinfunction "1_1") (pintype "passive"))
      (node (ref "HMI1") (pin "15") (pinfunction "15_15") (pintype "passive"))
      (node (ref "U$1") (pin "A0") (pinfunction "A0_A0") (pintype "bidirectional"))
    )
    (net (code "66") (name "/A1") (class "Default")
      (node (ref "ARD2") (pin "2") (pinfunction "2_2") (pintype "passive"))
      (node (ref "HMI1") (pin "13") (pinfunction "13_13") (pintype "passive"))
      (node (ref "U$1") (pin "A1") (pinfunction "A1_A1") (pintype "bidirectional"))
    )
    (net (code "67") (name "/A2") (class "Default")
      (node (ref "ARD2") (pin "3") (pinfunction "3_3") (pintype "passive"))
      (node (ref "HMI1") (pin "9") (pinfunction "9_9") (pintype "passive"))
      (node (ref "U$1") (pin "A2") (pinfunction "A2_A2") (pintype "bidirectional"))
    )
    (net (code "68") (name "/A3") (class "Default")
      (node (ref "ARD2") (pin "4") (pinfunction "4_4") (pintype "passive"))
      (node (ref "HMI1") (pin "7") (pinfunction "7_7") (pintype "passive"))
      (node (ref "U$1") (pin "A3") (pinfunction "A3_A3") (pintype "bidirectional"))
    )
    (net (code "69") (name "/A4") (class "Default")
      (node (ref "ARD2") (pin "5") (pinfunction "5_5") (pintype "passive"))
      (node (ref "HMI1") (pin "5") (pinfunction "5_5") (pintype "passive"))
      (node (ref "U$1") (pin "A4") (pinfunction "A4_A4") (pintype "bidirectional"))
    )
    (net (code "70") (name "/A5") (class "Default")
      (node (ref "ARD2") (pin "6") (pinfunction "6_6") (pintype "passive"))
      (node (ref "HMI1") (pin "3") (pinfunction "3_3") (pintype "passive"))
      (node (ref "U$1") (pin "A5") (pinfunction "A5_A5") (pintype "bidirectional"))
    )
    (net (code "71") (name "/A6") (class "Default")
      (node (ref "ARD2") (pin "7") (pinfunction "7_7") (pintype "passive"))
      (node (ref "U$1") (pin "A6") (pinfunction "A6_A6") (pintype "bidirectional"))
    )
    (net (code "72") (name "/A7") (class "Default")
      (node (ref "ARD2") (pin "8") (pinfunction "8_8") (pintype "passive"))
      (node (ref "U$1") (pin "A7") (pinfunction "A7_A7") (pintype "bidirectional"))
    )
    (net (code "73") (name "/A8") (class "Default")
      (node (ref "ARD3") (pin "1") (pinfunction "1_1") (pintype "passive"))
      (node (ref "U$1") (pin "A8") (pinfunction "A8_A8") (pintype "bidirectional"))
    )
    (net (code "74") (name "/A9") (class "Default")
      (node (ref "ARD3") (pin "2") (pinfunction "2_2") (pintype "passive"))
      (node (ref "U$1") (pin "A9") (pinfunction "A9_A9") (pintype "bidirectional"))
    )
    (net (code "75") (name "/A10") (class "Default")
      (node (ref "ARD3") (pin "3") (pinfunction "3_3") (pintype "passive"))
      (node (ref "U$1") (pin "A10") (pinfunction "A10_A10") (pintype "bidirectional"))
    )
    (net (code "76") (name "/A11") (class "Default")
      (node (ref "ARD3") (pin "4") (pinfunction "4_4") (pintype "passive"))
      (node (ref "U$1") (pin "A11") (pinfunction "A11_A11") (pintype "bidirectional"))
    )
    (net (code "77") (name "/AREF") (class "Default")
      (node (ref "ARD4") (pin "3") (pinfunction "3_3") (pintype "passive"))
      (node (ref "U$1") (pin "AREF") (pinfunction "AREF_AREF") (pintype "bidirectional"))
      (node (ref "U$1") (pin "AREF1") (pinfunction "AREF_AREF1") (pintype "bidirectional"))
    )
    (net (code "78") (name "/CANRX") (class "Default")
      (node (ref "ARD3") (pin "7") (pinfunction "7_7") (pintype "passive"))
      (node (ref "U$1") (pin "CANRX") (pinfunction "CANRX_CANRX") (pintype "bidirectional"))
    )
    (net (code "79") (name "/CANTX") (class "Default")
      (node (ref "ARD3") (pin "8") (pinfunction "8_8") (pintype "passive"))
      (node (ref "U$1") (pin "CANTX") (pinfunction "CANTX_CANTX") (pintype "bidirectional"))
    )
    (net (code "80") (name "/DAC0") (class "Default")
      (node (ref "ARD3") (pin "5") (pinfunction "5_5") (pintype "passive"))
      (node (ref "U$1") (pin "DAC0") (pinfunction "DAC0_DAC0") (pintype "bidirectional"))
    )
    (net (code "81") (name "/DAC1") (class "Default")
      (node (ref "ARD3") (pin "6") (pinfunction "6_6") (pintype "passive"))
      (node (ref "U$1") (pin "DAC1") (pinfunction "DAC1_DAC1") (pintype "bidirectional"))
    )
    (net (code "82") (name "/DEBUG-RESET") (class "Default")
      (node (ref "U$1") (pin "RESET_DEBUG") (pinfunction "RESET_DEBUG_RESET_DEBUG") (pintype "bidirectional"))
    )
    (net (code "83") (name "/DEBUG-SWCLK") (class "Default")
      (node (ref "U$1") (pin "SWCLK_DEBUG") (pinfunction "SWCLK_DEBUG_SWCLK_DEBUG") (pintype "bidirectional"))
    )
    (net (code "84") (name "/DEBUG-SWDIO") (class "Default")
      (node (ref "U$1") (pin "SWDIO_DEBUG") (pinfunction "SWDIO_DEBUG_SWDIO_DEBUG") (pintype "bidirectional"))
    )
    (net (code "85") (name "/EXTVCC1") (class "Default")
      (node (ref "MOSFETVCC1") (pin "1") (pinfunction "1_1") (pintype "passive"))
      (node (ref "VCCEXT1") (pin "P2") (pinfunction "2_P2") (pintype "passive"))
    )
    (net (code "86") (name "/EXTVCC2") (class "Default")
      (node (ref "MOSFETVCC2") (pin "1") (pinfunction "1_1") (pintype "passive"))
      (node (ref "VCCEXT2") (pin "P2") (pinfunction "2_P2") (pintype "passive"))
    )
    (net (code "87") (name "/EXTVCC3") (class "Default")
      (node (ref "MOSFETVCC3") (pin "1") (pinfunction "1_1") (pintype "passive"))
      (node (ref "VCCEXT3") (pin "P2") (pinfunction "2_P2") (pintype "passive"))
    )
    (net (code "88") (name "/EXTVCC4") (class "Default")
      (node (ref "MOSFETVCC4") (pin "1") (pinfunction "1_1") (pintype "passive"))
      (node (ref "VCCEXT4") (pin "P2") (pinfunction "2_P2") (pintype "passive"))
    )
    (net (code "89") (name "/EXTVCC5") (class "Default")
      (node (ref "MOSFETVCC5") (pin "1") (pinfunction "1_1") (pintype "passive"))
      (node (ref "VCCEXT5") (pin "P2") (pinfunction "2_P2") (pintype "passive"))
    )
    (net (code "90") (name "/EXTVCC6") (class "Default")
      (node (ref "MOSFETVCC6") (pin "1") (pinfunction "1_1") (pintype "passive"))
      (node (ref "VCCEXT6") (pin "P2") (pinfunction "2_P2") (pintype "passive"))
    )
    (net (code "91") (name "/GND") (class "Default")
      (node (ref "12DAC") (pin "5") (pinfunction "5_5") (pintype "passive"))
      (node (ref "12VIN") (pin "2") (pinfunction "2_2") (pintype "passive"))
      (node (ref "12VOUT1") (pin "2") (pinfunction "2_2") (pintype "passive"))
      (node (ref "12VOUT1") (pin "3") (pinfunction "3_3") (pintype "passive"))
      (node (ref "12VOUT2") (pin "2") (pinfunction "2_2") (pintype "passive"))
      (node (ref "12VOUT2") (pin "3") (pinfunction "3_3") (pintype "passive"))
      (node (ref "16ADC") (pin "9") (pinfunction "9_9") (pintype "passive"))
      (node (ref "16ADCCONFIG") (pin "5") (pinfunction "5_5") (pintype "passive"))
      (node (ref "16ADCIN1") (pin "1") (pinfunction "1_1") (pintype "passive"))
      (node (ref "16ADCIN1") (pin "3") (pinfunction "3_3") (pintype "passive"))
      (node (ref "16ADCIN1") (pin "5") (pinfunction "5_5") (pintype "passive"))
      (node (ref "16ADCIN1") (pin "7") (pinfunction "7_7") (pintype "passive"))
      (node (ref "16ADCIN2") (pin "2") (pinfunction "2_2") (pintype "passive"))
      (node (ref "16ADCIN2") (pin "3") (pinfunction "3_3") (pintype "passive"))
      (node (ref "16ADCIN3") (pin "2") (pinfunction "2_2") (pintype "passive"))
      (node (ref "16ADCIN3") (pin "3") (pinfunction "3_3") (pintype "passive"))
      (node (ref "ARD1") (pin "6") (pinfunction "6_6") (pintype "passive"))
      (node (ref "ARD1") (pin "7") (pinfunction "7_7") (pintype "passive"))
      (node (ref "ARD3V31") (pin "10") (pinfunction "10_10") (pintype "passive"))
      (node (ref "ARD3V31") (pin "12") (pinfunction "12_12") (pintype "passive"))
      (node (ref "ARD3V31") (pin "14") (pinfunction "14_14") (pintype "passive"))
      (node (ref "ARD3V31") (pin "16") (pinfunction "16_16") (pintype "passive"))
      (node (ref "ARD3V31") (pin "2") (pinfunction "2_2") (pintype "passive"))
      (node (ref "ARD3V31") (pin "4") (pinfunction "4_4") (pintype "passive"))
      (node (ref "ARD3V31") (pin "6") (pinfunction "6_6") (pintype "passive"))
      (node (ref "ARD3V31") (pin "8") (pinfunction "8_8") (pintype "passive"))
      (node (ref "ARD3V32") (pin "2") (pinfunction "2_2") (pintype "passive"))
      (node (ref "ARD3V32") (pin "3") (pinfunction "3_3") (pintype "passive"))
      (node (ref "ARD3V33") (pin "2") (pinfunction "2_2") (pintype "passive"))
      (node (ref "ARD3V33") (pin "3") (pinfunction "3_3") (pintype "passive"))
      (node (ref "ARD3V34") (pin "1") (pinfunction "1_1") (pintype "passive"))
      (node (ref "ARD3V34") (pin "3") (pinfunction "3_3") (pintype "passive"))
      (node (ref "ARD3V34") (pin "5") (pinfunction "5_5") (pintype "passive"))
      (node (ref "ARD3V34") (pin "7") (pinfunction "7_7") (pintype "passive"))
      (node (ref "ARD4") (pin "4") (pinfunction "4_4") (pintype "passive"))
      (node (ref "ARD5V1") (pin "1") (pinfunction "1_1") (pintype "passive"))
      (node (ref "ARD5V1") (pin "11") (pinfunction "11_11") (pintype "passive"))
      (node (ref "ARD5V1") (pin "13") (pinfunction "13_13") (pintype "passive"))
      (node (ref "ARD5V1") (pin "15") (pinfunction "15_15") (pintype "passive"))
      (node (ref "ARD5V1") (pin "3") (pinfunction "3_3") (pintype "passive"))
      (node (ref "ARD5V1") (pin "5") (pinfunction "5_5") (pintype "passive"))
      (node (ref "ARD5V1") (pin "7") (pinfunction "7_7") (pintype "passive"))
      (node (ref "ARD5V1") (pin "9") (pinfunction "9_9") (pintype "passive"))
      (node (ref "ARD5V2") (pin "2") (pinfunction "2_2") (pintype "passive"))
      (node (ref "ARD5V2") (pin "3") (pinfunction "3_3") (pintype "passive"))
      (node (ref "ARD5V3") (pin "2") (pinfunction "2_2") (pintype "passive"))
      (node (ref "ARD5V3") (pin "3") (pinfunction "3_3") (pintype "passive"))
      (node (ref "ARD7") (pin "1") (pinfunction "1_1") (pintype "passive"))
      (node (ref "ARD8") (pin "1") (pinfunction "1_1") (pintype "passive"))
      (node (ref "DEMUX") (pin "7") (pinfunction "GND_7") (pintype "power_in"))
      (node (ref "HMI1") (pin "11") (pinfunction "11_11") (pintype "passive"))
      (node (ref "HMI1") (pin "2") (pinfunction "2_2") (pintype "passive"))
      (node (ref "LEDR1") (pin "P$2") (pinfunction "2_P$2") (pintype "passive"))
      (node (ref "LIM1") (pin "2") (pinfunction "2_2") (pintype "passive"))
      (node (ref "LIM2") (pin "2") (pinfunction "2_2") (pintype "passive"))
      (node (ref "LIM3") (pin "2") (pinfunction "2_2") (pintype "passive"))
      (node (ref "LIM4") (pin "2") (pinfunction "2_2") (pintype "passive"))
      (node (ref "LSH3V31") (pin "1") (pinfunction "1_1") (pintype "passive"))
      (node (ref "LSH3V32") (pin "1") (pinfunction "1_1") (pintype "passive"))
      (node (ref "LSH3V33") (pin "1") (pinfunction "1_1") (pintype "passive"))
      (node (ref "LSH5V1") (pin "1") (pinfunction "1_1") (pintype "passive"))
      (node (ref "LSH5V2") (pin "1") (pinfunction "1_1") (pintype "passive"))
      (node (ref "LSH5V3") (pin "1") (pinfunction "1_1") (pintype "passive"))
      (node (ref "LSHOUT1") (pin "1") (pinfunction "1_1") (pintype "passive"))
      (node (ref "LSHOUT2") (pin "1") (pinfunction "1_1") (pintype "passive"))
      (node (ref "LSHOUT3") (pin "1") (pinfunction "1_1") (pintype "passive"))
      (node (ref "MOSFETIN1") (pin "3") (pinfunction "3_3") (pintype "passive"))
      (node (ref "MOSFETIN1") (pin "4") (pinfunction "4_4") (pintype "passive"))
      (node (ref "MOSFETIN2") (pin "3") (pinfunction "3_3") (pintype "passive"))
      (node (ref "MOSFETIN2") (pin "4") (pinfunction "4_4") (pintype "passive"))
      (node (ref "MOSFETIN3") (pin "3") (pinfunction "3_3") (pintype "passive"))
      (node (ref "MOSFETIN3") (pin "4") (pinfunction "4_4") (pintype "passive"))
      (node (ref "MOSFETIN4") (pin "3") (pinfunction "3_3") (pintype "passive"))
      (node (ref "MOSFETIN4") (pin "4") (pinfunction "4_4") (pintype "passive"))
      (node (ref "MOSFETIN5") (pin "3") (pinfunction "3_3") (pintype "passive"))
      (node (ref "MOSFETIN5") (pin "4") (pinfunction "4_4") (pintype "passive"))
      (node (ref "MOSFETIN6") (pin "3") (pinfunction "3_3") (pintype "passive"))
      (node (ref "MOSFETIN6") (pin "4") (pinfunction "4_4") (pintype "passive"))
      (node (ref "PZTOUT1") (pin "2") (pinfunction "2_2") (pintype "passive"))
      (node (ref "PZTOUT2") (pin "P2") (pinfunction "2_P2") (pintype "passive"))
      (node (ref "RESET") (pin "3") (pinfunction "2_3") (pintype "passive"))
      (node (ref "SPI1") (pin "5") (pinfunction "5_5") (pintype "bidirectional"))
      (node (ref "STEPPERC1") (pin "2") (pinfunction "2_2") (pintype "passive"))
      (node (ref "STEPPERC2") (pin "2") (pinfunction "2_2") (pintype "passive"))
      (node (ref "STEPPERC3") (pin "2") (pinfunction "2_2") (pintype "passive"))
      (node (ref "STEPPERC4") (pin "2") (pinfunction "2_2") (pintype "passive"))
      (node (ref "STEPPERDRV1") (pin "1") (pinfunction "1_1") (pintype "passive"))
      (node (ref "STEPPERDRV1") (pin "7") (pinfunction "7_7") (pintype "passive"))
      (node (ref "STEPPERDRV2") (pin "1") (pinfunction "1_1") (pintype "passive"))
      (node (ref "STEPPERDRV2") (pin "7") (pinfunction "7_7") (pintype "passive"))
      (node (ref "STEPPERDRV3") (pin "1") (pinfunction "1_1") (pintype "passive"))
      (node (ref "STEPPERDRV3") (pin "7") (pinfunction "7_7") (pintype "passive"))
      (node (ref "STEPPERDRV4") (pin "1") (pinfunction "1_1") (pintype "passive"))
      (node (ref "STEPPERDRV4") (pin "7") (pinfunction "7_7") (pintype "passive"))
      (node (ref "STEPPERGND1") (pin "1") (pinfunction "1_1") (pintype "passive"))
      (node (ref "STEPPERGND1") (pin "2") (pinfunction "2_2") (pintype "passive"))
      (node (ref "STEPPERGND1") (pin "3") (pinfunction "3_3") (pintype "passive"))
      (node (ref "STEPPERGND1") (pin "4") (pinfunction "4_4") (pintype "passive"))
      (node (ref "U$1") (pin "5V_ICSP") (pinfunction "5V_ICSP_5V_ICSP") (pintype "bidirectional"))
      (node (ref "U$1") (pin "GND1") (pinfunction "GND1_GND1") (pintype "bidirectional"))
      (node (ref "U$1") (pin "GND_1") (pinfunction "GND_1_GND_1") (pintype "bidirectional"))
      (node (ref "U$1") (pin "GND_2") (pinfunction "GND_2_GND_2") (pintype "bidirectional"))
      (node (ref "U$1") (pin "GND_A") (pinfunction "GND_A_GND_A") (pintype "bidirectional"))
      (node (ref "U$1") (pin "GND_B") (pinfunction "GND_B_GND_B") (pintype "bidirectional"))
      (node (ref "U$1") (pin "GND_DEBUG") (pinfunction "GND_DEBUG_GND_DEBUG") (pintype "bidirectional"))
      (node (ref "VCCEXT1") (pin "P1") (pinfunction "1_P1") (pintype "passive"))
      (node (ref "VCCEXT2") (pin "P1") (pinfunction "1_P1") (pintype "passive"))
      (node (ref "VCCEXT3") (pin "P1") (pinfunction "1_P1") (pintype "passive"))
      (node (ref "VCCEXT4") (pin "P1") (pinfunction "1_P1") (pintype "passive"))
      (node (ref "VCCEXT5") (pin "P1") (pinfunction "1_P1") (pintype "passive"))
      (node (ref "VCCEXT6") (pin "P1") (pinfunction "1_P1") (pintype "passive"))
      (node (ref "VCCOUT2") (pin "2") (pinfunction "2_2") (pintype "passive"))
      (node (ref "VCCOUT2") (pin "3") (pinfunction "3_3") (pintype "passive"))
      (node (ref "VCCOUT3") (pin "2") (pinfunction "2_2") (pintype "passive"))
      (node (ref "VCCOUT3") (pin "3") (pinfunction "3_3") (pintype "passive"))
      (node (ref "VCCOUT4") (pin "2") (pinfunction "2_2") (pintype "passive"))
      (node (ref "VCCOUT4") (pin "3") (pinfunction "3_3") (pintype "passive"))
      (node (ref "VCCOUT6") (pin "2") (pinfunction "2_2") (pintype "passive"))
      (node (ref "VCCOUT6") (pin "3") (pinfunction "3_3") (pintype "passive"))
      (node (ref "VCCOUT7") (pin "2") (pinfunction "2_2") (pintype "passive"))
      (node (ref "VCCOUT7") (pin "3") (pinfunction "3_3") (pintype "passive"))
      (node (ref "VCCOUT8") (pin "2") (pinfunction "2_2") (pintype "passive"))
      (node (ref "VCCOUT8") (pin "3") (pinfunction "3_3") (pintype "passive"))
      (node (ref "VCCREG1") (pin "2") (pinfunction "2_2") (pintype "passive"))
      (node (ref "VCCREG2") (pin "2") (pinfunction "2_2") (pintype "passive"))
      (node (ref "VCCREG3") (pin "2") (pinfunction "2_2") (pintype "passive"))
      (node (ref "VCCREG4") (pin "2") (pinfunction "2_2") (pintype "passive"))
      (node (ref "VCCREG5") (pin "2") (pinfunction "2_2") (pintype "passive"))
      (node (ref "VCCREG6") (pin "2") (pinfunction "2_2") (pintype "passive"))
    )
    (net (code "92") (name "/IOREF") (class "Default")
      (node (ref "ARD1") (pin "2") (pinfunction "2_2") (pintype "passive"))
      (node (ref "U$1") (pin "IOREF") (pinfunction "IOREF_IOREF") (pintype "bidirectional"))
    )
    (net (code "93") (name "/MISO") (class "Default")
      (node (ref "SPI1") (pin "2") (pinfunction "2_2") (pintype "bidirectional"))
      (node (ref "U$1") (pin "MISO_ICSP") (pinfunction "MISO_ICSP_MISO_ICSP") (pintype "bidirectional"))
    )
    (net (code "94") (name "/MOSFETVCC1") (class "Default")
      (node (ref "MOSFETIN1") (pin "1") (pinfunction "1_1") (pintype "passive"))
      (node (ref "MOSFETIN1") (pin "2") (pinfunction "2_2") (pintype "passive"))
      (node (ref "MOSFETVCC1") (pin "2") (pinfunction "2_2") (pintype "passive"))
    )
    (net (code "95") (name "/MOSFETVCC2") (class "Default")
      (node (ref "MOSFETIN2") (pin "1") (pinfunction "1_1") (pintype "passive"))
      (node (ref "MOSFETIN2") (pin "2") (pinfunction "2_2") (pintype "passive"))
      (node (ref "MOSFETVCC2") (pin "2") (pinfunction "2_2") (pintype "passive"))
    )
    (net (code "96") (name "/MOSFETVCC3") (class "Default")
      (node (ref "MOSFETIN3") (pin "1") (pinfunction "1_1") (pintype "passive"))
      (node (ref "MOSFETIN3") (pin "2") (pinfunction "2_2") (pintype "passive"))
      (node (ref "MOSFETVCC3") (pin "2") (pinfunction "2_2") (pintype "passive"))
    )
    (net (code "97") (name "/MOSFETVCC4") (class "Default")
      (node (ref "MOSFETIN4") (pin "1") (pinfunction "1_1") (pintype "passive"))
      (node (ref "MOSFETIN4") (pin "2") (pinfunction "2_2") (pintype "passive"))
      (node (ref "MOSFETVCC4") (pin "2") (pinfunction "2_2") (pintype "passive"))
    )
    (net (code "98") (name "/MOSFETVCC5") (class "Default")
      (node (ref "MOSFETIN5") (pin "1") (pinfunction "1_1") (pintype "passive"))
      (node (ref "MOSFETIN5") (pin "2") (pinfunction "2_2") (pintype "passive"))
      (node (ref "MOSFETVCC5") (pin "2") (pinfunction "2_2") (pintype "passive"))
    )
    (net (code "99") (name "/MOSFETVCC6") (class "Default")
      (node (ref "MOSFETIN6") (pin "1") (pinfunction "1_1") (pintype "passive"))
      (node (ref "MOSFETIN6") (pin "2") (pinfunction "2_2") (pintype "passive"))
      (node (ref "MOSFETVCC6") (pin "2") (pinfunction "2_2") (pintype "passive"))
    )
    (net (code "100") (name "/MOSI") (class "Default")
      (node (ref "SPI1") (pin "3") (pinfunction "3_3") (pintype "bidirectional"))
      (node (ref "U$1") (pin "MOSI_ICSP") (pinfunction "MOSI_ICSP_MOSI_ICSP") (pintype "bidirectional"))
    )
    (net (code "101") (name "/REGVCC1") (class "Default")
      (node (ref "MOSFETVCC1") (pin "3") (pinfunction "3_3") (pintype "passive"))
      (node (ref "VCCOUT4") (pin "4") (pinfunction "4_4") (pintype "passive"))
      (node (ref "VCCOUT8") (pin "4") (pinfunction "4_4") (pintype "passive"))
      (node (ref "VCCREG1") (pin "1") (pinfunction "1_1") (pintype "passive"))
    )
    (net (code "102") (name "/REGVCC2") (class "Default")
      (node (ref "MOSFETVCC2") (pin "3") (pinfunction "3_3") (pintype "passive"))
      (node (ref "VCCOUT4") (pin "1") (pinfunction "1_1") (pintype "passive"))
      (node (ref "VCCOUT8") (pin "1") (pinfunction "1_1") (pintype "passive"))
      (node (ref "VCCREG2") (pin "1") (pinfunction "1_1") (pintype "passive"))
    )
    (net (code "103") (name "/REGVCC3") (class "Default")
      (node (ref "MOSFETVCC3") (pin "3") (pinfunction "3_3") (pintype "passive"))
      (node (ref "VCCOUT3") (pin "4") (pinfunction "4_4") (pintype "passive"))
      (node (ref "VCCOUT7") (pin "4") (pinfunction "4_4") (pintype "passive"))
      (node (ref "VCCREG3") (pin "1") (pinfunction "1_1") (pintype "passive"))
    )
    (net (code "104") (name "/REGVCC4") (class "Default")
      (node (ref "MOSFETVCC4") (pin "3") (pinfunction "3_3") (pintype "passive"))
      (node (ref "VCCOUT3") (pin "1") (pinfunction "1_1") (pintype "passive"))
      (node (ref "VCCOUT7") (pin "1") (pinfunction "1_1") (pintype "passive"))
      (node (ref "VCCREG4") (pin "1") (pinfunction "1_1") (pintype "passive"))
    )
    (net (code "105") (name "/REGVCC5") (class "Default")
      (node (ref "MOSFETVCC5") (pin "3") (pinfunction "3_3") (pintype "passive"))
      (node (ref "VCCOUT2") (pin "4") (pinfunction "4_4") (pintype "passive"))
      (node (ref "VCCOUT6") (pin "4") (pinfunction "4_4") (pintype "passive"))
      (node (ref "VCCREG5") (pin "1") (pinfunction "1_1") (pintype "passive"))
    )
    (net (code "106") (name "/REGVCC6") (class "Default")
      (node (ref "MOSFETVCC6") (pin "3") (pinfunction "3_3") (pintype "passive"))
      (node (ref "VCCOUT2") (pin "1") (pinfunction "1_1") (pintype "passive"))
      (node (ref "VCCOUT6") (pin "1") (pinfunction "1_1") (pintype "passive"))
      (node (ref "VCCREG6") (pin "1") (pinfunction "1_1") (pintype "passive"))
    )
    (net (code "107") (name "/RESET") (class "Default")
      (node (ref "ARD1") (pin "3") (pinfunction "3_3") (pintype "passive"))
      (node (ref "RESET") (pin "1") (pinfunction "1_1") (pintype "passive"))
      (node (ref "U$1") (pin "RESET") (pinfunction "RESET_RESET") (pintype "bidirectional"))
    )
    (net (code "108") (name "/RX0(D0)") (class "Default")
      (node (ref "ARD5") (pin "8") (pinfunction "8_8") (pintype "passive"))
      (node (ref "U$1") (pin "RX0") (pinfunction "RX0_RX0") (pintype "bidirectional"))
    )
    (net (code "109") (name "/RX1(19)") (class "Default")
      (node (ref "ARD6") (pin "6") (pinfunction "6_6") (pintype "passive"))
      (node (ref "DEMUX") (pin "10") (pinfunction "4B_10") (pintype "input"))
      (node (ref "DEMUX") (pin "2") (pinfunction "1B_2") (pintype "input"))
      (node (ref "DEMUX") (pin "3") (pinfunction "2B_3") (pintype "input"))
      (node (ref "DEMUX") (pin "9") (pinfunction "3B_9") (pintype "input"))
      (node (ref "U$1") (pin "RX1") (pinfunction "RX1_RX1") (pintype "bidirectional"))
      (node (ref "UARTR1") (pin "2") (pinfunction "2_2") (pintype "passive"))
    )
    (net (code "110") (name "/RX2(17)") (class "Default")
      (node (ref "ARD6") (pin "4") (pinfunction "4_4") (pintype "passive"))
      (node (ref "LSH3V31") (pin "3") (pinfunction "3_3") (pintype "passive"))
      (node (ref "U$1") (pin "RX2") (pinfunction "RX2_RX2") (pintype "bidirectional"))
    )
    (net (code "111") (name "/RX3(15)") (class "Default")
      (node (ref "ARD6") (pin "2") (pinfunction "2_2") (pintype "passive"))
      (node (ref "HMI1") (pin "16") (pinfunction "16_16") (pintype "passive"))
      (node (ref "U$1") (pin "RX3") (pinfunction "RX3_RX3") (pintype "bidirectional"))
    )
    (net (code "112") (name "/RX25V") (class "Default")
      (node (ref "LSH5V1") (pin "3") (pinfunction "3_3") (pintype "passive"))
      (node (ref "LSHOUT1") (pin "3") (pinfunction "3_3") (pintype "passive"))
    )
    (net (code "113") (name "/SCK") (class "Default")
      (node (ref "SPI1") (pin "4") (pinfunction "4_4") (pintype "bidirectional"))
      (node (ref "U$1") (pin "SCK_ICSP") (pinfunction "SCK_ICSP_SCK_ICSP") (pintype "bidirectional"))
    )
    (net (code "114") (name "/SCL(21)") (class "Default")
      (node (ref "ARD6") (pin "8") (pinfunction "8_8") (pintype "passive"))
      (node (ref "I2C3V3") (pin "1") (pinfunction "1_1") (pintype "passive"))
      (node (ref "I2C3V3") (pin "3") (pinfunction "3_3") (pintype "passive"))
      (node (ref "I2C3V3") (pin "5") (pinfunction "5_5") (pintype "passive"))
      (node (ref "I2C3V3") (pin "7") (pinfunction "7_7") (pintype "passive"))
      (node (ref "LSH3V31") (pin "5") (pinfunction "5_5") (pintype "passive"))
      (node (ref "U$1") (pin "SCL") (pinfunction "SCL_SCL") (pintype "bidirectional"))
    )
    (net (code "115") (name "/SCL1") (class "Default")
      (node (ref "ARD4") (pin "1") (pinfunction "1_1") (pintype "passive"))
      (node (ref "U$1") (pin "SCL1") (pinfunction "SCL1_SCL1") (pintype "bidirectional"))
    )
    (net (code "116") (name "/SCL5V") (class "Default")
      (node (ref "12DAC") (pin "4") (pinfunction "4_4") (pintype "passive"))
      (node (ref "16ADC") (pin "8") (pinfunction "8_8") (pintype "passive"))
      (node (ref "16ADCCONFIG") (pin "4") (pinfunction "4_4") (pintype "passive"))
      (node (ref "I2C5V") (pin "1") (pinfunction "1_1") (pintype "passive"))
      (node (ref "I2C5V") (pin "3") (pinfunction "3_3") (pintype "passive"))
      (node (ref "I2C5V") (pin "5") (pinfunction "5_5") (pintype "passive"))
      (node (ref "I2C5V") (pin "7") (pinfunction "7_7") (pintype "passive"))
      (node (ref "LSH5V1") (pin "5") (pinfunction "5_5") (pintype "passive"))
      (node (ref "LSHOUT1") (pin "5") (pinfunction "5_5") (pintype "passive"))
    )
    (net (code "117") (name "/SDA(20)") (class "Default")
      (node (ref "ARD6") (pin "7") (pinfunction "7_7") (pintype "passive"))
      (node (ref "I2C3V3") (pin "2") (pinfunction "2_2") (pintype "passive"))
      (node (ref "I2C3V3") (pin "4") (pinfunction "4_4") (pintype "passive"))
      (node (ref "I2C3V3") (pin "6") (pinfunction "6_6") (pintype "passive"))
      (node (ref "I2C3V3") (pin "8") (pinfunction "8_8") (pintype "passive"))
      (node (ref "LSH3V31") (pin "4") (pinfunction "4_4") (pintype "passive"))
      (node (ref "U$1") (pin "SDA") (pinfunction "SDA_SDA") (pintype "bidirectional"))
    )
    (net (code "118") (name "/SDA1") (class "Default")
      (node (ref "ARD4") (pin "2") (pinfunction "2_2") (pintype "passive"))
      (node (ref "U$1") (pin "SDA1") (pinfunction "SDA1_SDA1") (pintype "bidirectional"))
    )
    (net (code "119") (name "/SDA5V") (class "Default")
      (node (ref "12DAC") (pin "3") (pinfunction "3_3") (pintype "passive"))
      (node (ref "16ADC") (pin "7") (pinfunction "7_7") (pintype "passive"))
      (node (ref "16ADCCONFIG") (pin "3") (pinfunction "3_3") (pintype "passive"))
      (node (ref "I2C5V") (pin "2") (pinfunction "2_2") (pintype "passive"))
      (node (ref "I2C5V") (pin "4") (pinfunction "4_4") (pintype "passive"))
      (node (ref "I2C5V") (pin "6") (pinfunction "6_6") (pintype "passive"))
      (node (ref "I2C5V") (pin "8") (pinfunction "8_8") (pintype "passive"))
      (node (ref "LSH5V1") (pin "4") (pinfunction "4_4") (pintype "passive"))
      (node (ref "LSHOUT1") (pin "4") (pinfunction "4_4") (pintype "passive"))
    )
    (net (code "120") (name "/SPIRESET") (class "Default")
      (node (ref "SPI1") (pin "6") (pinfunction "6_6") (pintype "bidirectional"))
      (node (ref "U$1") (pin "RESET_ICSP") (pinfunction "RESET_ICSP_RESET_ICSP") (pintype "bidirectional"))
    )
    (net (code "121") (name "/STEPEN1") (class "Default")
      (node (ref "STEPPEREN1") (pin "1") (pinfunction "1_1") (pintype "passive"))
      (node (ref "STEPPERIN1") (pin "8") (pinfunction "8_8") (pintype "passive"))
    )
    (net (code "122") (name "/STEPEN2") (class "Default")
      (node (ref "STEPPEREN1") (pin "2") (pinfunction "2_2") (pintype "passive"))
      (node (ref "STEPPERIN2") (pin "8") (pinfunction "8_8") (pintype "passive"))
    )
    (net (code "123") (name "/STEPEN3") (class "Default")
      (node (ref "STEPPEREN1") (pin "3") (pinfunction "3_3") (pintype "passive"))
      (node (ref "STEPPERIN3") (pin "8") (pinfunction "8_8") (pintype "passive"))
    )
    (net (code "124") (name "/STEPEN4") (class "Default")
      (node (ref "STEPPEREN1") (pin "4") (pinfunction "4_4") (pintype "passive"))
      (node (ref "STEPPERIN4") (pin "8") (pinfunction "8_8") (pintype "passive"))
    )
    (net (code "125") (name "/STEPM1A1") (class "Default")
      (node (ref "STEPPERDRV1") (pin "4") (pinfunction "4_4") (pintype "passive"))
      (node (ref "STEPPEROUT1") (pin "2") (pinfunction "2_2") (pintype "passive"))
    )
    (net (code "126") (name "/STEPM1A2") (class "Default")
      (node (ref "STEPPERDRV2") (pin "4") (pinfunction "4_4") (pintype "passive"))
      (node (ref "STEPPEROUT2") (pin "2") (pinfunction "2_2") (pintype "passive"))
    )
    (net (code "127") (name "/STEPM1A3") (class "Default")
      (node (ref "STEPPERDRV3") (pin "4") (pinfunction "4_4") (pintype "passive"))
      (node (ref "STEPPEROUT3") (pin "2") (pinfunction "2_2") (pintype "passive"))
    )
    (net (code "128") (name "/STEPM1A4") (class "Default")
      (node (ref "STEPPERDRV4") (pin "4") (pinfunction "4_4") (pintype "passive"))
      (node (ref "STEPPEROUT4") (pin "2") (pinfunction "2_2") (pintype "passive"))
    )
    (net (code "129") (name "/STEPM1B1") (class "Default")
      (node (ref "STEPPERDRV1") (pin "3") (pinfunction "3_3") (pintype "passive"))
      (node (ref "STEPPEROUT1") (pin "1") (pinfunction "1_1") (pintype "passive"))
    )
    (net (code "130") (name "/STEPM1B2") (class "Default")
      (node (ref "STEPPERDRV2") (pin "3") (pinfunction "3_3") (pintype "passive"))
      (node (ref "STEPPEROUT2") (pin "1") (pinfunction "1_1") (pintype "passive"))
    )
    (net (code "131") (name "/STEPM1B3") (class "Default")
      (node (ref "STEPPERDRV3") (pin "3") (pinfunction "3_3") (pintype "passive"))
      (node (ref "STEPPEROUT3") (pin "1") (pinfunction "1_1") (pintype "passive"))
    )
    (net (code "132") (name "/STEPM1B4") (class "Default")
      (node (ref "STEPPERDRV4") (pin "3") (pinfunction "3_3") (pintype "passive"))
      (node (ref "STEPPEROUT4") (pin "1") (pinfunction "1_1") (pintype "passive"))
    )
    (net (code "133") (name "/STEPM2A1") (class "Default")
      (node (ref "STEPPERDRV1") (pin "5") (pinfunction "5_5") (pintype "passive"))
      (node (ref "STEPPEROUT1") (pin "3") (pinfunction "3_3") (pintype "passive"))
    )
    (net (code "134") (name "/STEPM2A2") (class "Default")
      (node (ref "STEPPERDRV2") (pin "5") (pinfunction "5_5") (pintype "passive"))
      (node (ref "STEPPEROUT2") (pin "3") (pinfunction "3_3") (pintype "passive"))
    )
    (net (code "135") (name "/STEPM2A3") (class "Default")
      (node (ref "STEPPERDRV3") (pin "5") (pinfunction "5_5") (pintype "passive"))
      (node (ref "STEPPEROUT3") (pin "3") (pinfunction "3_3") (pintype "passive"))
    )
    (net (code "136") (name "/STEPM2A4") (class "Default")
      (node (ref "STEPPERDRV4") (pin "5") (pinfunction "5_5") (pintype "passive"))
      (node (ref "STEPPEROUT4") (pin "3") (pinfunction "3_3") (pintype "passive"))
    )
    (net (code "137") (name "/STEPM2B1") (class "Default")
      (node (ref "STEPPERDRV1") (pin "6") (pinfunction "6_6") (pintype "passive"))
      (node (ref "STEPPEROUT1") (pin "4") (pinfunction "4_4") (pintype "passive"))
    )
    (net (code "138") (name "/STEPM2B2") (class "Default")
      (node (ref "STEPPERDRV2") (pin "6") (pinfunction "6_6") (pintype "passive"))
      (node (ref "STEPPEROUT2") (pin "4") (pinfunction "4_4") (pintype "passive"))
    )
    (net (code "139") (name "/STEPM2B3") (class "Default")
      (node (ref "STEPPERDRV3") (pin "6") (pinfunction "6_6") (pintype "passive"))
      (node (ref "STEPPEROUT3") (pin "4") (pinfunction "4_4") (pintype "passive"))
    )
    (net (code "140") (name "/STEPM2B4") (class "Default")
      (node (ref "STEPPERDRV4") (pin "6") (pinfunction "6_6") (pintype "passive"))
      (node (ref "STEPPEROUT4") (pin "4") (pinfunction "4_4") (pintype "passive"))
    )
    (net (code "141") (name "/STEPUART1") (class "Default")
      (node (ref "DEMUX") (pin "11") (pinfunction "4A_11") (pintype "input"))
      (node (ref "STEPPERIN1") (pin "3") (pinfunction "3_3") (pintype "passive"))
      (node (ref "STEPPERIN1") (pin "4") (pinfunction "4_4") (pintype "passive"))
    )
    (net (code "142") (name "/STEPUART2") (class "Default")
      (node (ref "DEMUX") (pin "8") (pinfunction "3A_8") (pintype "input"))
      (node (ref "STEPPERIN2") (pin "3") (pinfunction "3_3") (pintype "passive"))
      (node (ref "STEPPERIN2") (pin "4") (pinfunction "4_4") (pintype "passive"))
    )
    (net (code "143") (name "/STEPUART3") (class "Default")
      (node (ref "DEMUX") (pin "1") (pinfunction "1A_1") (pintype "input"))
      (node (ref "STEPPERIN3") (pin "3") (pinfunction "3_3") (pintype "passive"))
      (node (ref "STEPPERIN3") (pin "4") (pinfunction "4_4") (pintype "passive"))
    )
    (net (code "144") (name "/STEPUART4") (class "Default")
      (node (ref "DEMUX") (pin "4") (pinfunction "2A_4") (pintype "input"))
      (node (ref "STEPPERIN4") (pin "3") (pinfunction "3_3") (pintype "passive"))
      (node (ref "STEPPERIN4") (pin "4") (pinfunction "4_4") (pintype "passive"))
    )
    (net (code "145") (name "/TX0(D1)") (class "Default")
      (node (ref "ARD5") (pin "7") (pinfunction "7_7") (pintype "passive"))
      (node (ref "U$1") (pin "TX0") (pinfunction "TX0_TX0") (pintype "bidirectional"))
    )
    (net (code "146") (name "/TX1(18)") (class "Default")
      (node (ref "ARD6") (pin "5") (pinfunction "5_5") (pintype "passive"))
      (node (ref "U$1") (pin "TX1") (pinfunction "TX1_TX1") (pintype "bidirectional"))
      (node (ref "UARTR1") (pin "1") (pinfunction "1_1") (pintype "passive"))
    )
    (net (code "147") (name "/TX2(16)") (class "Default")
      (node (ref "ARD6") (pin "3") (pinfunction "3_3") (pintype "passive"))
      (node (ref "LSH3V31") (pin "2") (pinfunction "2_2") (pintype "passive"))
      (node (ref "U$1") (pin "TX2") (pinfunction "TX2_TX2") (pintype "bidirectional"))
    )
    (net (code "148") (name "/TX3(14)") (class "Default")
      (node (ref "ARD6") (pin "1") (pinfunction "1_1") (pintype "passive"))
      (node (ref "HMI1") (pin "14") (pinfunction "14_14") (pintype "passive"))
      (node (ref "U$1") (pin "TX3") (pinfunction "TX3_TX3") (pintype "bidirectional"))
    )
    (net (code "149") (name "/TX25V") (class "Default")
      (node (ref "LSH5V1") (pin "2") (pinfunction "2_2") (pintype "passive"))
      (node (ref "LSHOUT1") (pin "2") (pinfunction "2_2") (pintype "passive"))
    )
    (net (code "150") (name "/VIN") (class "Default")
      (node (ref "ARD1") (pin "8") (pinfunction "8_8") (pintype "passive"))
      (node (ref "U$1") (pin "VIN") (pinfunction "VIN_VIN") (pintype "bidirectional"))
    )
    (net (code "151") (name "Net-(LED1-C)") (class "Default")
      (node (ref "LED1") (pin "K") (pinfunction "C_K") (pintype "passive"))
      (node (ref "LEDR1") (pin "P$1") (pinfunction "1_P$1") (pintype "passive"))
    )
    (net (code "152") (name "unconnected-(12VIN-Pad3)") (class "Default")
      (node (ref "12VIN") (pin "3") (pinfunction "3_3") (pintype "passive"))
    )
    (net (code "153") (name "unconnected-(12VSWITCH-Pad3)") (class "Default")
      (node (ref "12VSWITCH") (pin "3") (pinfunction "3_3") (pintype "passive"))
    )
    (net (code "154") (name "unconnected-(ARD1-Pad1)") (class "Default")
      (node (ref "ARD1") (pin "1") (pinfunction "1_1") (pintype "passive"))
    )
    (net (code "155") (name "unconnected-(STEPPERIN1-Pad5)") (class "Default")
      (node (ref "STEPPERIN1") (pin "5") (pinfunction "5_5") (pintype "passive"))
    )
    (net (code "156") (name "unconnected-(STEPPERIN1-Pad6)") (class "Default")
      (node (ref "STEPPERIN1") (pin "6") (pinfunction "6_6") (pintype "passive"))
    )
    (net (code "157") (name "unconnected-(STEPPERIN1-Pad7)") (class "Default")
      (node (ref "STEPPERIN1") (pin "7") (pinfunction "7_7") (pintype "passive"))
    )
    (net (code "158") (name "unconnected-(STEPPERIN2-Pad5)") (class "Default")
      (node (ref "STEPPERIN2") (pin "5") (pinfunction "5_5") (pintype "passive"))
    )
    (net (code "159") (name "unconnected-(STEPPERIN2-Pad6)") (class "Default")
      (node (ref "STEPPERIN2") (pin "6") (pinfunction "6_6") (pintype "passive"))
    )
    (net (code "160") (name "unconnected-(STEPPERIN2-Pad7)") (class "Default")
      (node (ref "STEPPERIN2") (pin "7") (pinfunction "7_7") (pintype "passive"))
    )
    (net (code "161") (name "unconnected-(STEPPERIN3-Pad5)") (class "Default")
      (node (ref "STEPPERIN3") (pin "5") (pinfunction "5_5") (pintype "passive"))
    )
    (net (code "162") (name "unconnected-(STEPPERIN3-Pad6)") (class "Default")
      (node (ref "STEPPERIN3") (pin "6") (pinfunction "6_6") (pintype "passive"))
    )
    (net (code "163") (name "unconnected-(STEPPERIN3-Pad7)") (class "Default")
      (node (ref "STEPPERIN3") (pin "7") (pinfunction "7_7") (pintype "passive"))
    )
    (net (code "164") (name "unconnected-(STEPPERIN4-Pad5)") (class "Default")
      (node (ref "STEPPERIN4") (pin "5") (pinfunction "5_5") (pintype "passive"))
    )
    (net (code "165") (name "unconnected-(STEPPERIN4-Pad6)") (class "Default")
      (node (ref "STEPPERIN4") (pin "6") (pinfunction "6_6") (pintype "passive"))
    )
    (net (code "166") (name "unconnected-(STEPPERIN4-Pad7)") (class "Default")
      (node (ref "STEPPERIN4") (pin "7") (pinfunction "7_7") (pintype "passive"))
    )
    (net (code "167") (name "unconnected-(U$1-PadNC)") (class "Default")
      (node (ref "U$1") (pin "NC") (pinfunction "NC_NC") (pintype "bidirectional"))
    )
    (net (code "168") (name "unconnected-(VCCREG1-Pad4)") (class "Default")
      (node (ref "VCCREG1") (pin "4") (pinfunction "4_4") (pintype "passive"))
    )
    (net (code "169") (name "unconnected-(VCCREG1-Pad5)") (class "Default")
      (node (ref "VCCREG1") (pin "5") (pinfunction "5_5") (pintype "passive"))
    )
    (net (code "170") (name "unconnected-(VCCREG2-Pad4)") (class "Default")
      (node (ref "VCCREG2") (pin "4") (pinfunction "4_4") (pintype "passive"))
    )
    (net (code "171") (name "unconnected-(VCCREG2-Pad5)") (class "Default")
      (node (ref "VCCREG2") (pin "5") (pinfunction "5_5") (pintype "passive"))
    )
    (net (code "172") (name "unconnected-(VCCREG3-Pad4)") (class "Default")
      (node (ref "VCCREG3") (pin "4") (pinfunction "4_4") (pintype "passive"))
    )
    (net (code "173") (name "unconnected-(VCCREG3-Pad5)") (class "Default")
      (node (ref "VCCREG3") (pin "5") (pinfunction "5_5") (pintype "passive"))
    )
    (net (code "174") (name "unconnected-(VCCREG4-Pad4)") (class "Default")
      (node (ref "VCCREG4") (pin "4") (pinfunction "4_4") (pintype "passive"))
    )
    (net (code "175") (name "unconnected-(VCCREG4-Pad5)") (class "Default")
      (node (ref "VCCREG4") (pin "5") (pinfunction "5_5") (pintype "passive"))
    )
    (net (code "176") (name "unconnected-(VCCREG5-Pad4)") (class "Default")
      (node (ref "VCCREG5") (pin "4") (pinfunction "4_4") (pintype "passive"))
    )
    (net (code "177") (name "unconnected-(VCCREG5-Pad5)") (class "Default")
      (node (ref "VCCREG5") (pin "5") (pinfunction "5_5") (pintype "passive"))
    )
    (net (code "178") (name "unconnected-(VCCREG6-Pad4)") (class "Default")
      (node (ref "VCCREG6") (pin "4") (pinfunction "4_4") (pintype "passive"))
    )
    (net (code "179") (name "unconnected-(VCCREG6-Pad5)") (class "Default")
      (node (ref "VCCREG6") (pin "5") (pinfunction "5_5") (pintype "passive"))
    )
  )
)
